# Matrix_Game_Board.net
KiCad netlist of a schematic drawn in EAGLE
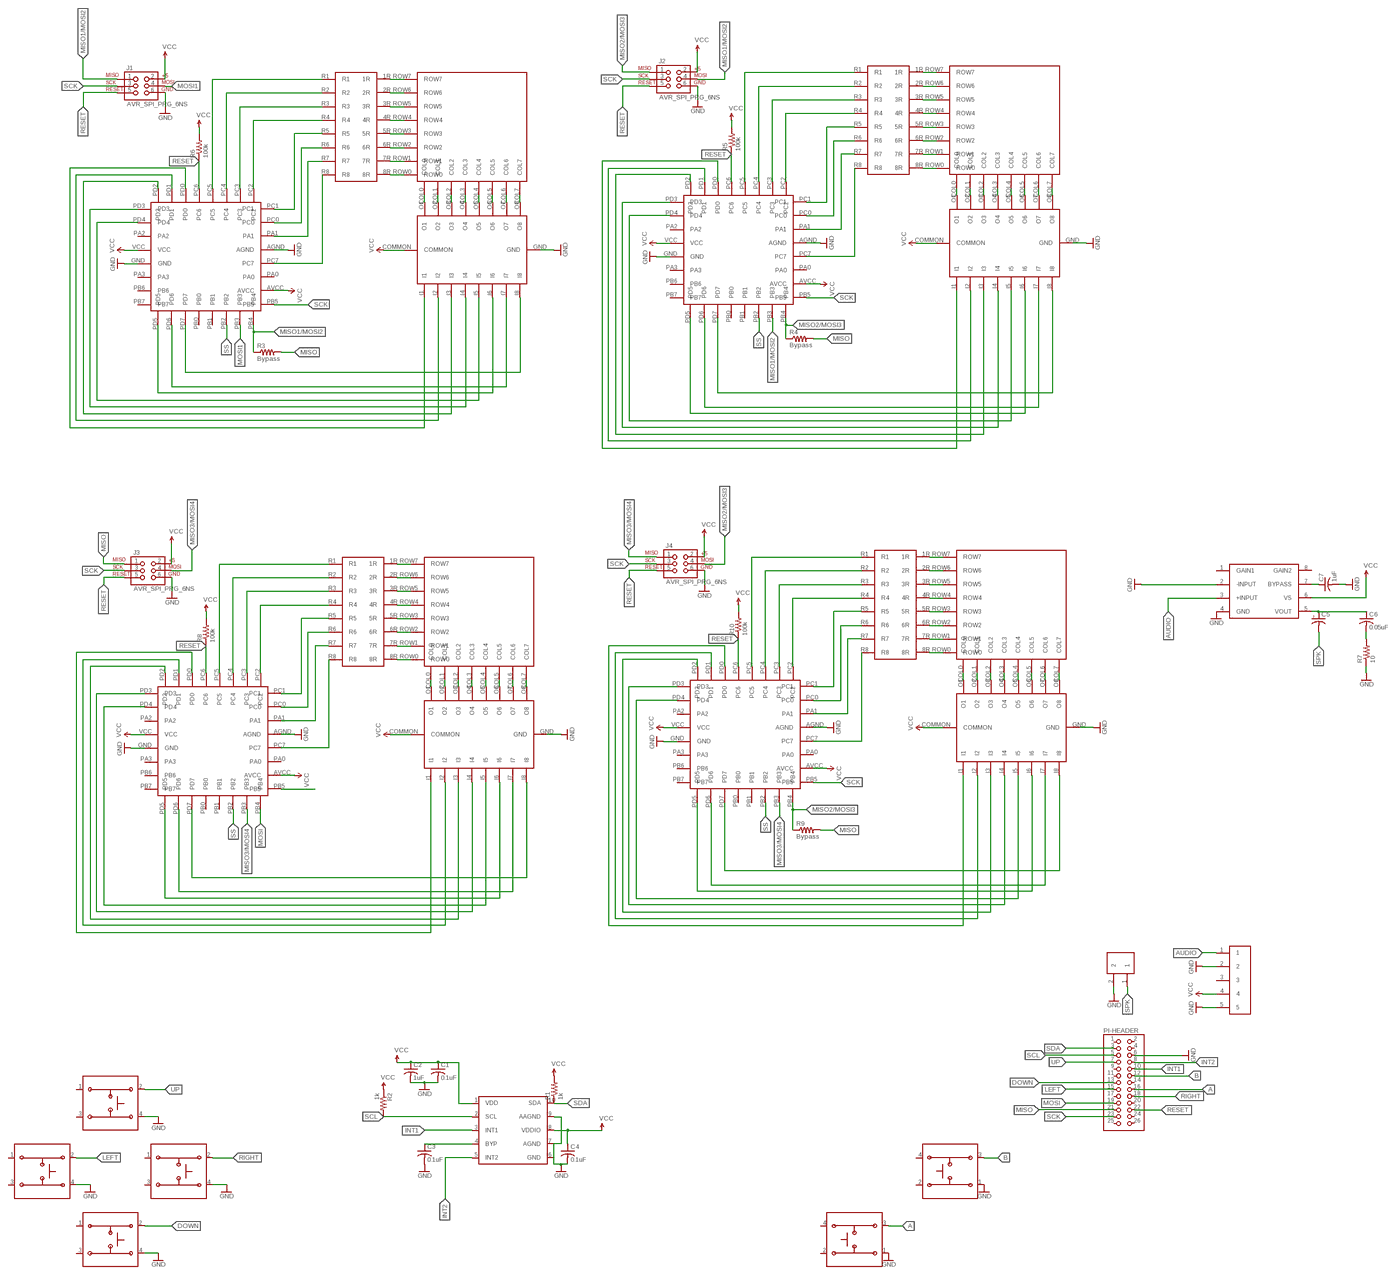
[diagram p0: schematic, sheet 1, overview]
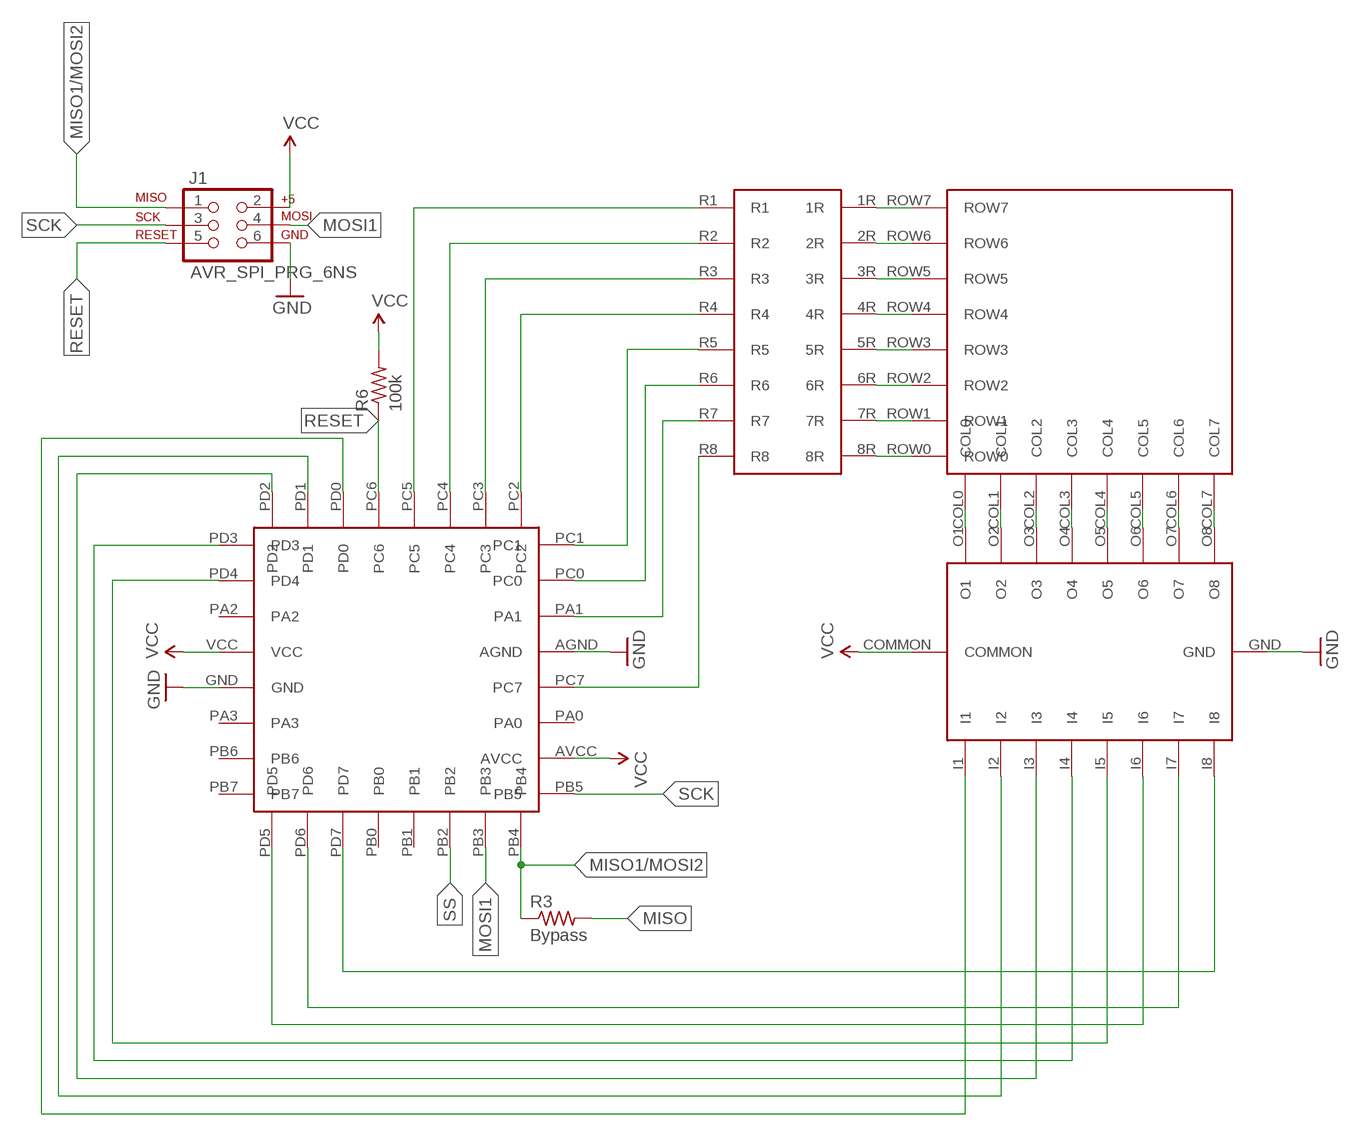
[diagram p1: schematic, sheet 1, part 1 of 4]
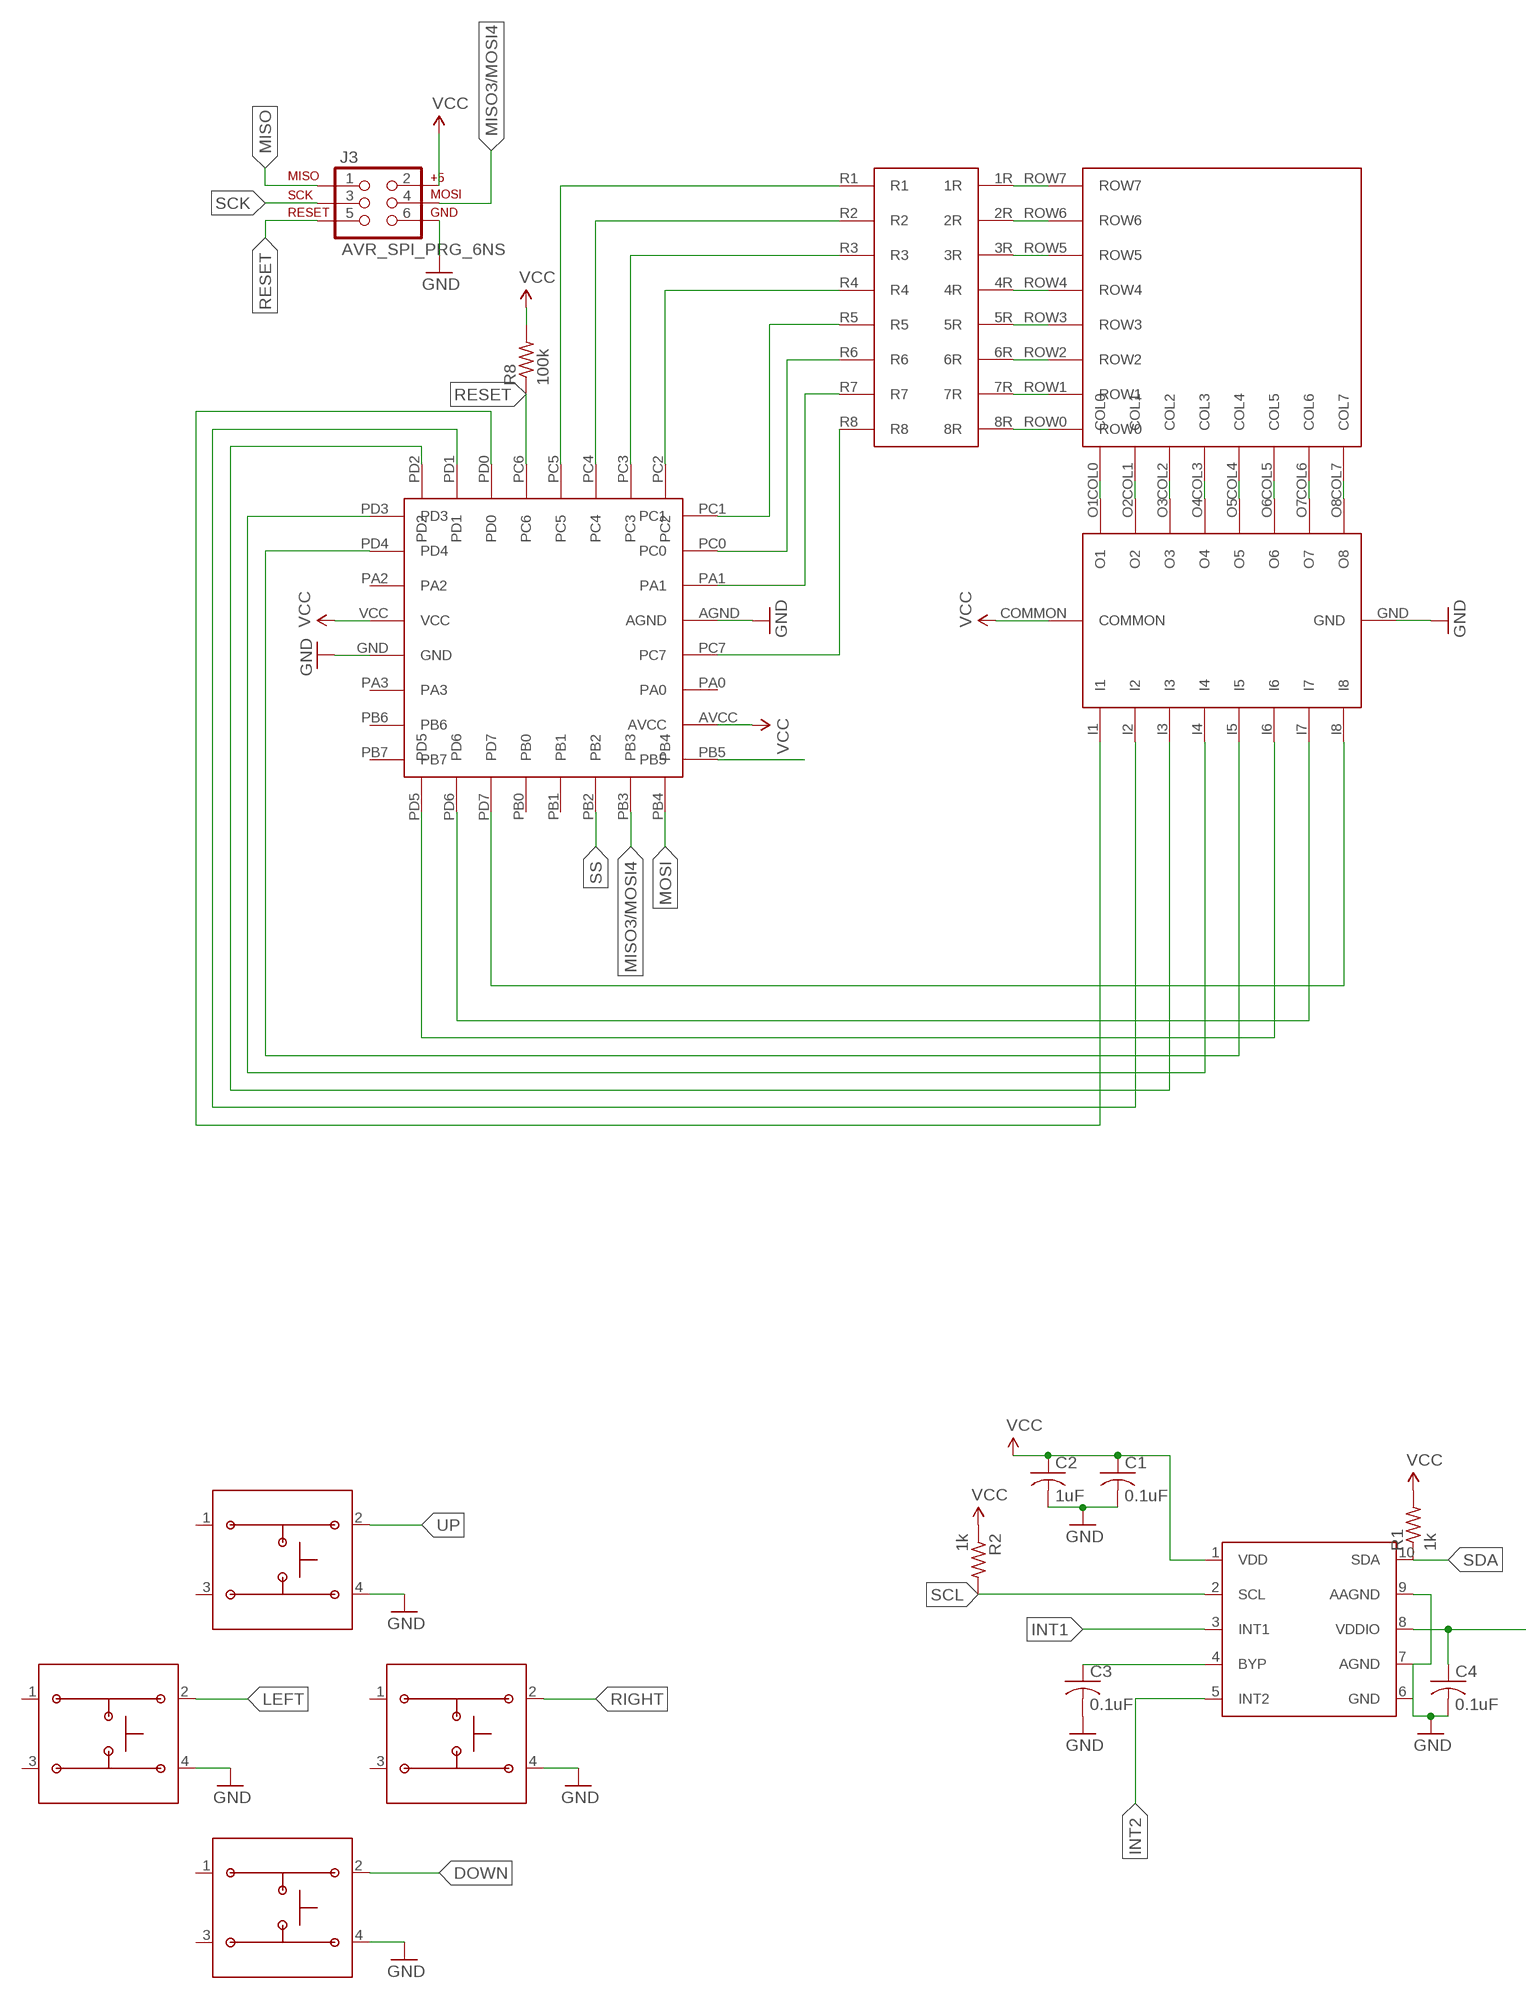
[diagram p2: schematic, sheet 1, part 2 of 4]
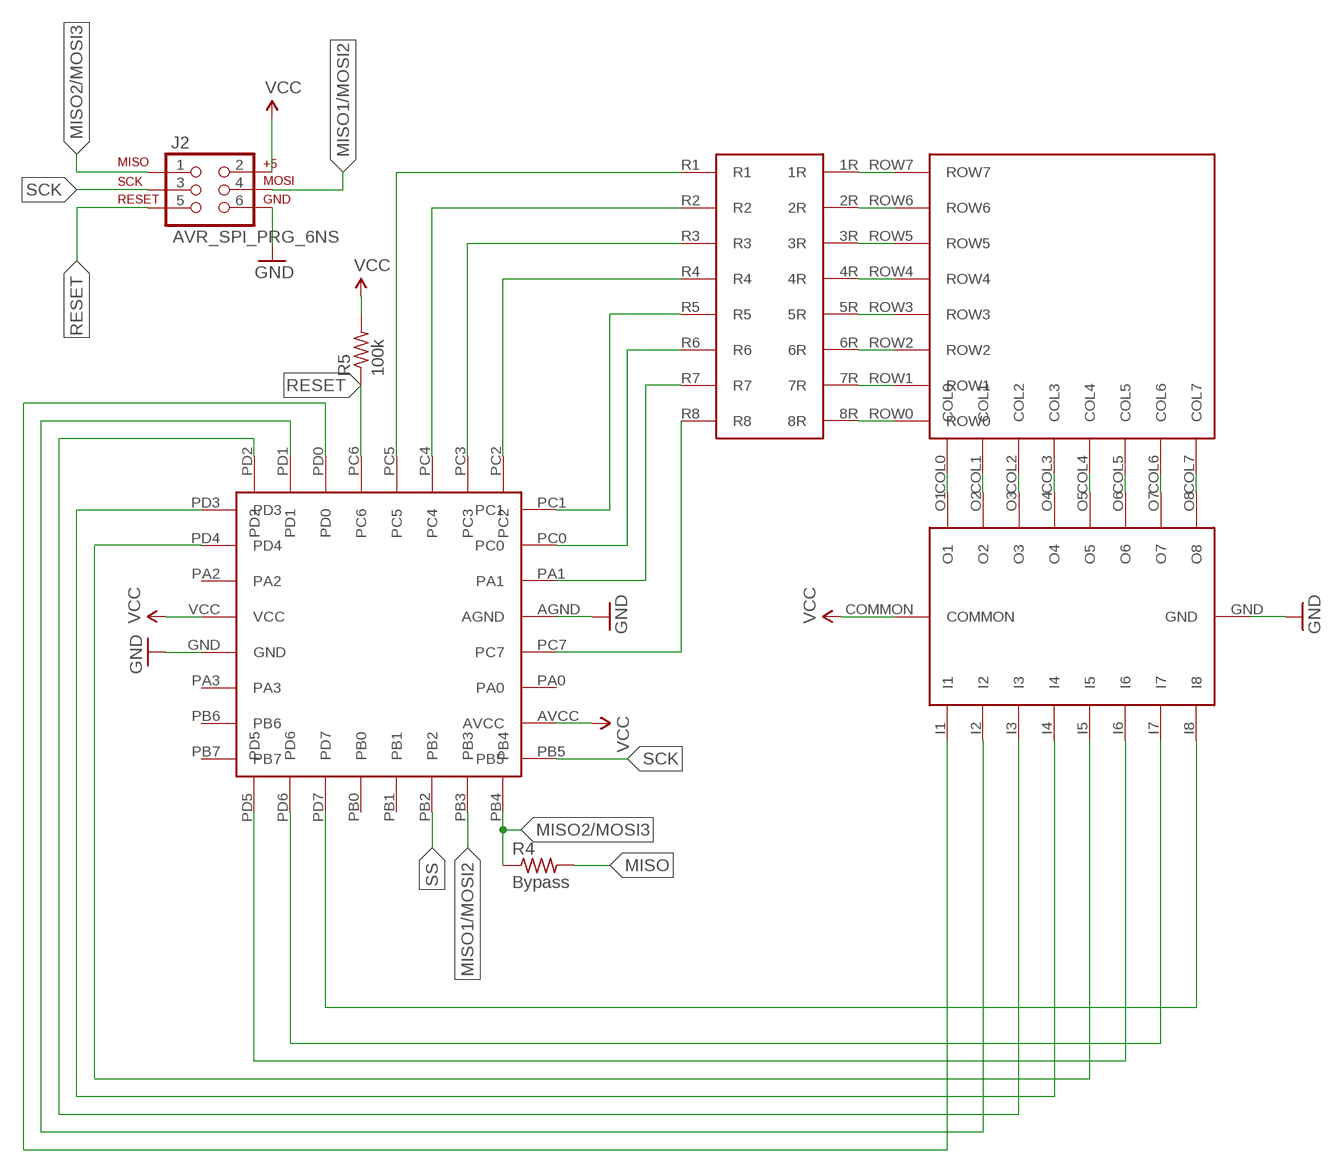
[diagram p3: schematic, sheet 1, part 3 of 4]
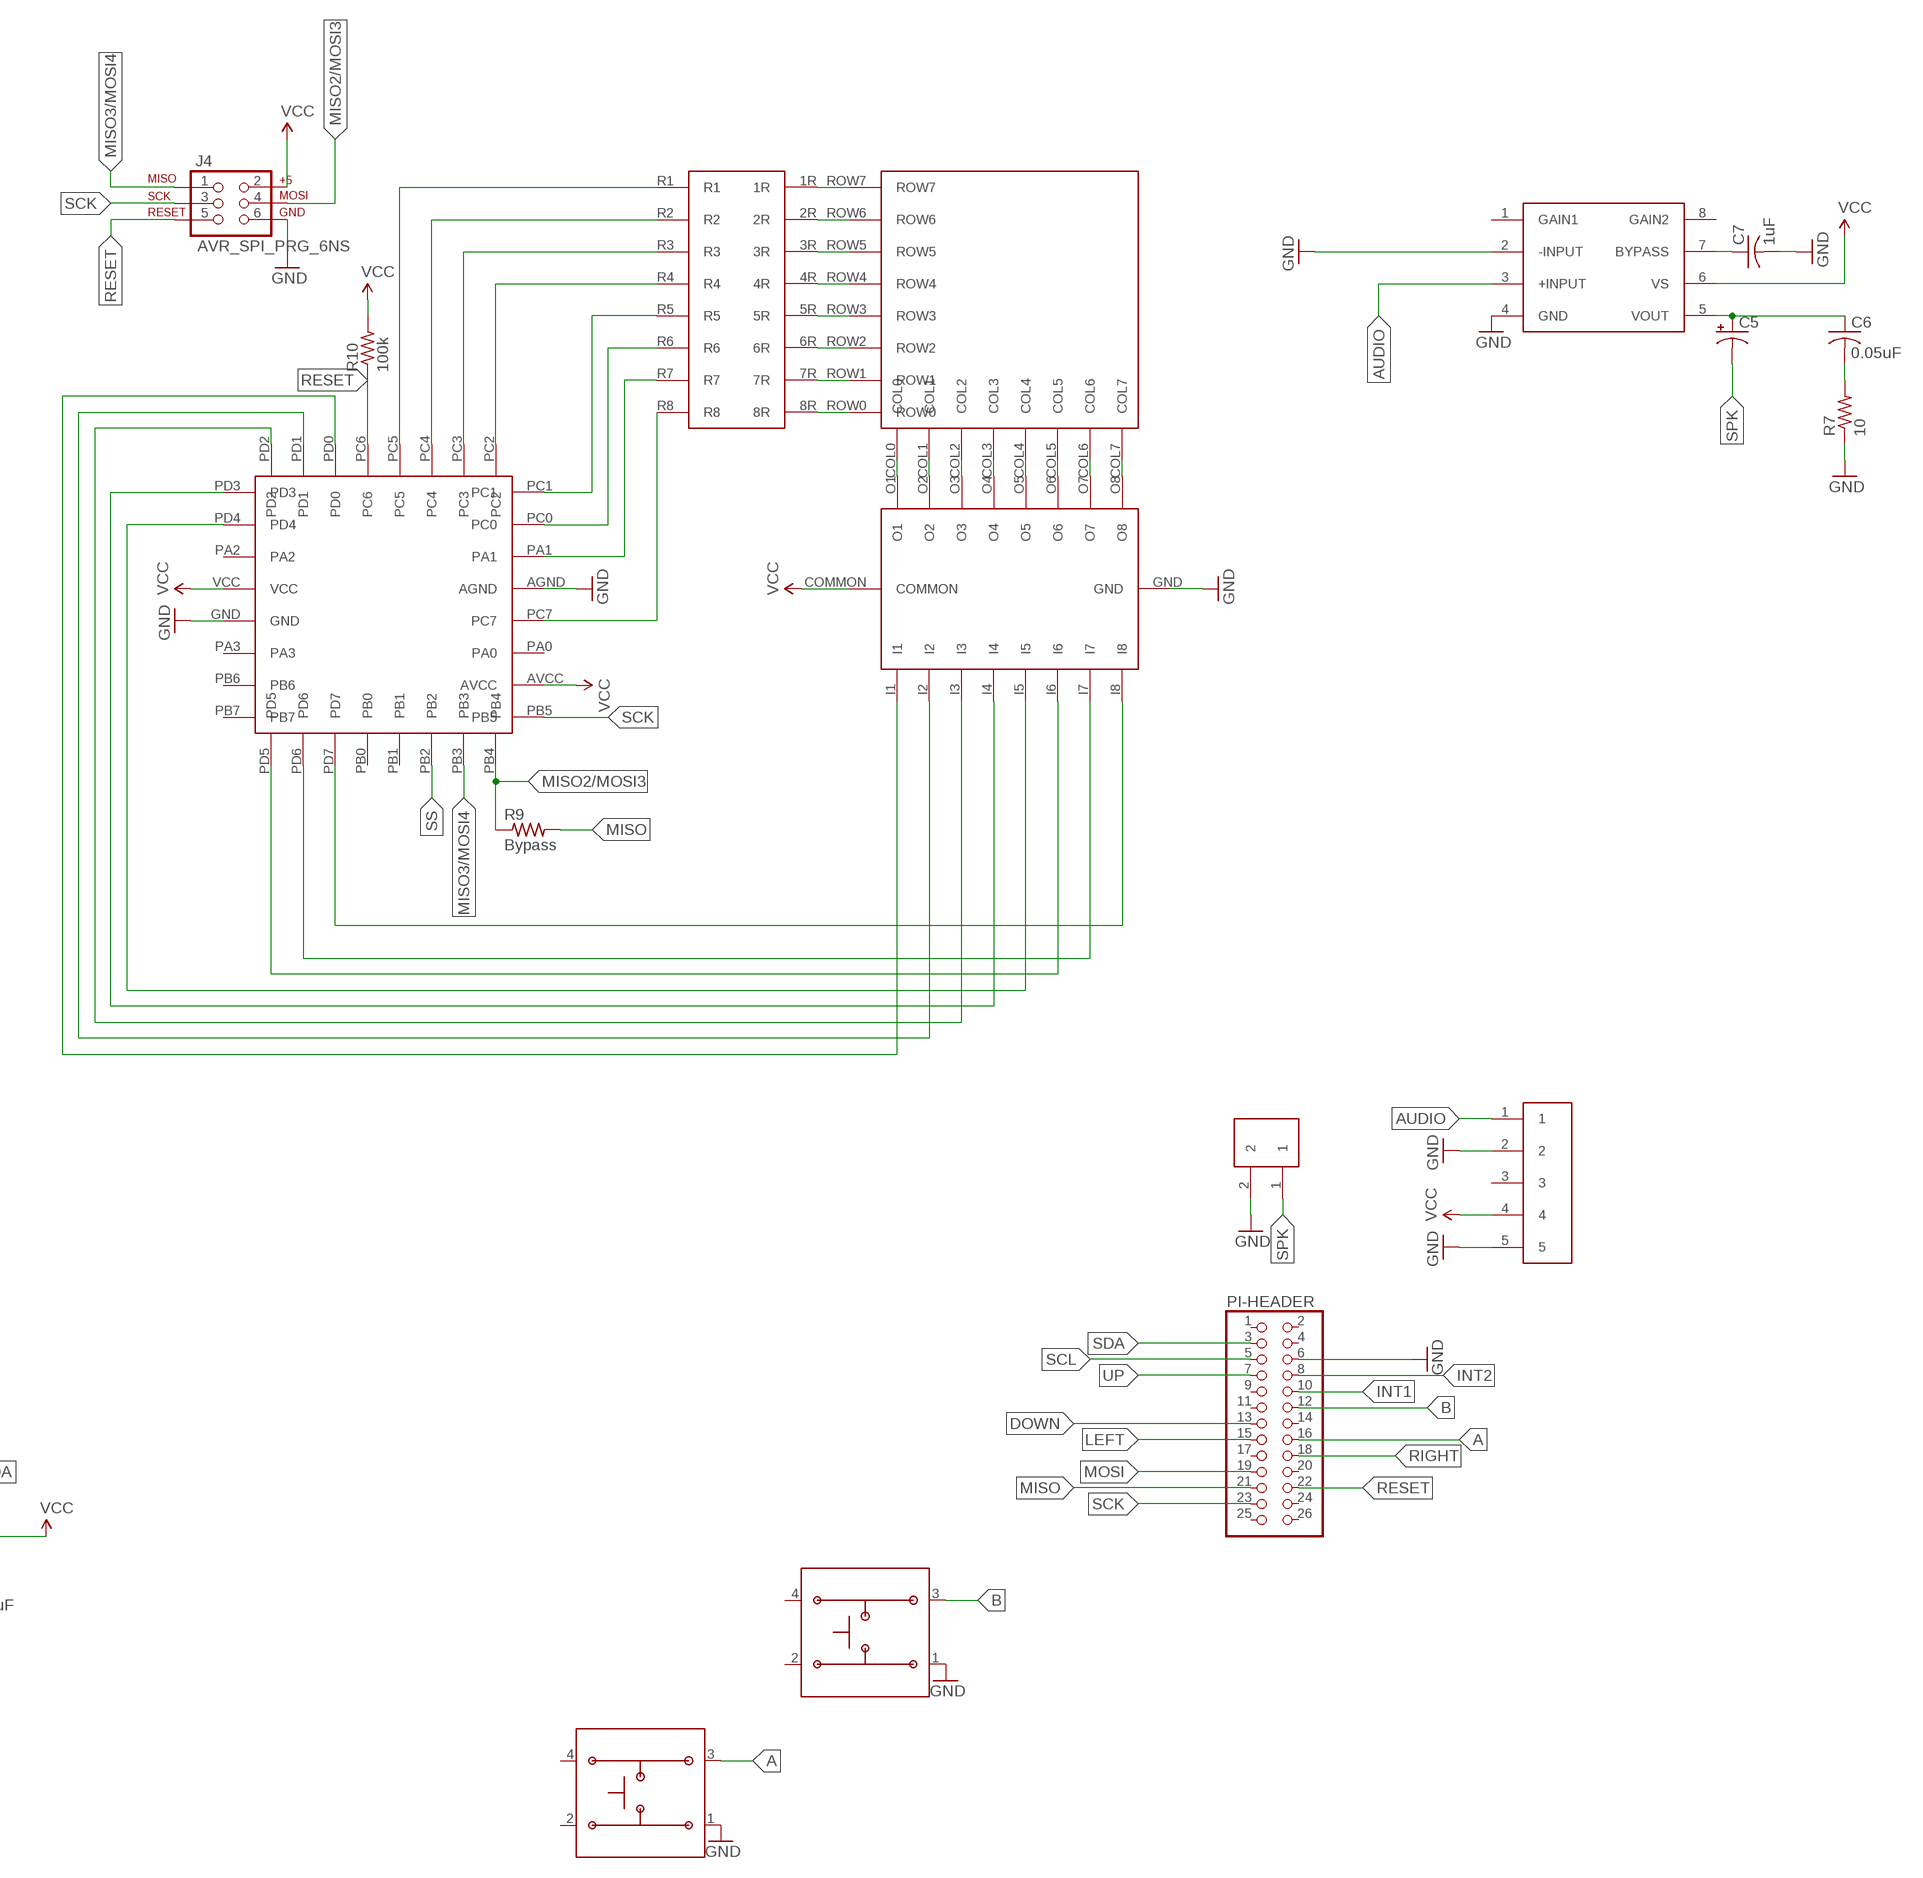
[diagram p4: schematic, sheet 1, part 4 of 4]

(export (version "E")
  (design (tool "Eeschema 10.0.6"))
  (components
    (comp (ref "C1")
      (value "0.1uF")
      (footprint "eagle-import:C0603")
      (libsource (lib "eagle-import") (part "C-USC0603"))
    )
    (comp (ref "C2")
      (value "1uF")
      (footprint "eagle-import:C0603")
      (libsource (lib "eagle-import") (part "C-USC0603"))
    )
    (comp (ref "C3")
      (value "0.1uF")
      (footprint "eagle-import:C0603")
      (libsource (lib "eagle-import") (part "C-USC0603"))
    )
    (comp (ref "C4")
      (value "0.1uF")
      (footprint "eagle-import:C0603")
      (libsource (lib "eagle-import") (part "C-USC0603"))
    )
    (comp (ref "C5")
      (value "CPOL-US153CLV-0605")
      (footprint "eagle-import:153CLV-0605")
      (libsource (lib "eagle-import") (part "CPOL-US153CLV-0605"))
    )
    (comp (ref "C6")
      (value "0.05uF")
      (footprint "eagle-import:C0603")
      (libsource (lib "eagle-import") (part "C-USC0603"))
    )
    (comp (ref "C7")
      (value "1uF")
      (footprint "eagle-import:C0603")
      (libsource (lib "eagle-import") (part "C-USC0603"))
    )
    (comp (ref "J1")
      (value "AVR_SPI_PRG_6NS")
      (footprint "eagle-import:2X3-NS")
      (libsource (lib "eagle-import") (part "AVR_SPI_PRG_6NS"))
    )
    (comp (ref "J2")
      (value "AVR_SPI_PRG_6NS")
      (footprint "eagle-import:2X3-NS")
      (libsource (lib "eagle-import") (part "AVR_SPI_PRG_6NS"))
    )
    (comp (ref "J3")
      (value "AVR_SPI_PRG_6NS")
      (footprint "eagle-import:2X3-NS")
      (libsource (lib "eagle-import") (part "AVR_SPI_PRG_6NS"))
    )
    (comp (ref "J4")
      (value "AVR_SPI_PRG_6NS")
      (footprint "eagle-import:2X3-NS")
      (libsource (lib "eagle-import") (part "AVR_SPI_PRG_6NS"))
    )
    (comp (ref "PI-HEADER")
      (value "PINHD-2X13")
      (footprint "eagle-import:2X13")
      (libsource (lib "eagle-import") (part "PINHD-2X13"))
    )
    (comp (ref "R1")
      (value "1k")
      (footprint "eagle-import:R0603")
      (libsource (lib "eagle-import") (part "R-US_R0603"))
    )
    (comp (ref "R2")
      (value "1k")
      (footprint "eagle-import:R0603")
      (libsource (lib "eagle-import") (part "R-US_R0603"))
    )
    (comp (ref "R3")
      (value "Bypass")
      (footprint "eagle-import:R0805")
      (libsource (lib "eagle-import") (part "R-US_R0805"))
    )
    (comp (ref "R4")
      (value "Bypass")
      (footprint "eagle-import:R0805")
      (libsource (lib "eagle-import") (part "R-US_R0805"))
    )
    (comp (ref "R5")
      (value "100k")
      (footprint "eagle-import:R0805")
      (libsource (lib "eagle-import") (part "R-US_R0805"))
    )
    (comp (ref "R6")
      (value "100k")
      (footprint "eagle-import:R0805")
      (libsource (lib "eagle-import") (part "R-US_R0805"))
    )
    (comp (ref "R7")
      (value "10")
      (footprint "eagle-import:R0603")
      (libsource (lib "eagle-import") (part "R-US_R0603"))
    )
    (comp (ref "R8")
      (value "100k")
      (footprint "eagle-import:R0805")
      (libsource (lib "eagle-import") (part "R-US_R0805"))
    )
    (comp (ref "R9")
      (value "Bypass")
      (footprint "eagle-import:R0805")
      (libsource (lib "eagle-import") (part "R-US_R0805"))
    )
    (comp (ref "R10")
      (value "100k")
      (footprint "eagle-import:R0805")
      (libsource (lib "eagle-import") (part "R-US_R0805"))
    )
    (comp (ref "U$1")
      (value "8X8_LED_MATRIX")
      (footprint "eagle-import:8X8_LED_MATRIX")
      (libsource (lib "eagle-import") (part "8X8_LED_MATRIX"))
    )
    (comp (ref "U$2")
      (value "RES_ARRAY")
      (footprint "eagle-import:RES_ARRAY")
      (libsource (lib "eagle-import") (part "RES_ARRAY"))
    )
    (comp (ref "U$3")
      (value "8X8_LED_MATRIX")
      (footprint "eagle-import:8X8_LED_MATRIX")
      (libsource (lib "eagle-import") (part "8X8_LED_MATRIX"))
    )
    (comp (ref "U$4")
      (value "ULN2803AFWG")
      (footprint "eagle-import:ULN2803AFWG")
      (libsource (lib "eagle-import") (part "ULN2803AFWG"))
    )
    (comp (ref "U$5")
      (value "ULN2803AFWG")
      (footprint "eagle-import:ULN2803AFWG")
      (libsource (lib "eagle-import") (part "ULN2803AFWG"))
    )
    (comp (ref "U$6")
      (value "ATTINY48")
      (footprint "eagle-import:ATTINY48")
      (libsource (lib "eagle-import") (part "ATTINY48"))
    )
    (comp (ref "U$7")
      (value "RES_ARRAY")
      (footprint "eagle-import:RES_ARRAY")
      (libsource (lib "eagle-import") (part "RES_ARRAY"))
    )
    (comp (ref "U$8")
      (value "8X8_LED_MATRIX")
      (footprint "eagle-import:8X8_LED_MATRIX")
      (libsource (lib "eagle-import") (part "8X8_LED_MATRIX"))
    )
    (comp (ref "U$9")
      (value "ATTINY48")
      (footprint "eagle-import:ATTINY48")
      (libsource (lib "eagle-import") (part "ATTINY48"))
    )
    (comp (ref "U$10")
      (value "ULN2803AFWG")
      (footprint "eagle-import:ULN2803AFWG")
      (libsource (lib "eagle-import") (part "ULN2803AFWG"))
    )
    (comp (ref "U$11")
      (value "ATTINY48")
      (footprint "eagle-import:ATTINY48")
      (libsource (lib "eagle-import") (part "ATTINY48"))
    )
    (comp (ref "U$12")
      (value "RES_ARRAY")
      (footprint "eagle-import:RES_ARRAY")
      (libsource (lib "eagle-import") (part "RES_ARRAY"))
    )
    (comp (ref "U$13")
      (value "8X8_LED_MATRIX")
      (footprint "eagle-import:8X8_LED_MATRIX")
      (libsource (lib "eagle-import") (part "8X8_LED_MATRIX"))
    )
    (comp (ref "U$14")
      (value "ULN2803AFWG")
      (footprint "eagle-import:ULN2803AFWG")
      (libsource (lib "eagle-import") (part "ULN2803AFWG"))
    )
    (comp (ref "U$15")
      (value "ATTINY48")
      (footprint "eagle-import:ATTINY48")
      (libsource (lib "eagle-import") (part "ATTINY48"))
    )
    (comp (ref "U$16")
      (value "RES_ARRAY")
      (footprint "eagle-import:RES_ARRAY")
      (libsource (lib "eagle-import") (part "RES_ARRAY"))
    )
    (comp (ref "U$17")
      (value "12X12MM_BUTTON")
      (footprint "eagle-import:12X12MM_BUTTON")
      (libsource (lib "eagle-import") (part "12X12MM_BUTTON"))
    )
    (comp (ref "U$18")
      (value "12X12MM_BUTTON")
      (footprint "eagle-import:12X12MM_BUTTON")
      (libsource (lib "eagle-import") (part "12X12MM_BUTTON"))
    )
    (comp (ref "U$19")
      (value "12X12MM_BUTTON")
      (footprint "eagle-import:12X12MM_BUTTON")
      (libsource (lib "eagle-import") (part "12X12MM_BUTTON"))
    )
    (comp (ref "U$20")
      (value "12X12MM_BUTTON")
      (footprint "eagle-import:12X12MM_BUTTON")
      (libsource (lib "eagle-import") (part "12X12MM_BUTTON"))
    )
    (comp (ref "U$21")
      (value "12X12MM_BUTTON")
      (footprint "eagle-import:12X12MM_BUTTON")
      (libsource (lib "eagle-import") (part "12X12MM_BUTTON"))
    )
    (comp (ref "U$22")
      (value "12X12MM_BUTTON")
      (footprint "eagle-import:12X12MM_BUTTON")
      (libsource (lib "eagle-import") (part "12X12MM_BUTTON"))
    )
    (comp (ref "U$23")
      (value "MMA8653FCR1")
      (footprint "eagle-import:MMA8653FCR1")
      (libsource (lib "eagle-import") (part "MMA8653FCR1"))
    )
    (comp (ref "U$25")
      (value "LM386")
      (footprint "eagle-import:LM386")
      (libsource (lib "eagle-import") (part "LM386"))
    )
    (comp (ref "U$29")
      (value "DF3_1X2")
      (footprint "eagle-import:DF3_1X2")
      (libsource (lib "eagle-import") (part "DF3_1X2"))
    )
    (comp (ref "U$30")
      (value "DF3_1X5")
      (footprint "eagle-import:DF3_1X5")
      (libsource (lib "eagle-import") (part "DF3_1X5"))
    )
  )
  (nets
    (net (code "1") (name "A") (class "Default")
      (node (ref "PI-HEADER") (pin "16") (pinfunction "16_16") (pintype "passive"))
      (node (ref "U$22") (pin "3") (pinfunction "3_3") (pintype "bidirectional"))
    )
    (net (code "2") (name "AUDIO") (class "Default")
      (node (ref "U$25") (pin "3") (pinfunction "+INPUT_3") (pintype "bidirectional"))
      (node (ref "U$30") (pin "1") (pinfunction "1_1") (pintype "bidirectional"))
    )
    (net (code "3") (name "B") (class "Default")
      (node (ref "PI-HEADER") (pin "12") (pinfunction "12_12") (pintype "passive"))
      (node (ref "U$21") (pin "3") (pinfunction "3_3") (pintype "bidirectional"))
    )
    (net (code "4") (name "DOWN") (class "Default")
      (node (ref "PI-HEADER") (pin "13") (pinfunction "13_13") (pintype "passive"))
      (node (ref "U$20") (pin "2") (pinfunction "2_2") (pintype "bidirectional"))
    )
    (net (code "5") (name "GND") (class "Default")
      (node (ref "C1") (pin "2") (pinfunction "2_2") (pintype "passive"))
      (node (ref "C2") (pin "2") (pinfunction "2_2") (pintype "passive"))
      (node (ref "C3") (pin "2") (pinfunction "2_2") (pintype "passive"))
      (node (ref "C4") (pin "2") (pinfunction "2_2") (pintype "passive"))
      (node (ref "C7") (pin "2") (pinfunction "2_2") (pintype "passive"))
      (node (ref "J1") (pin "6") (pinfunction "6_6") (pintype "passive"))
      (node (ref "J2") (pin "6") (pinfunction "6_6") (pintype "passive"))
      (node (ref "J3") (pin "6") (pinfunction "6_6") (pintype "passive"))
      (node (ref "J4") (pin "6") (pinfunction "6_6") (pintype "passive"))
      (node (ref "PI-HEADER") (pin "6") (pinfunction "6_6") (pintype "passive"))
      (node (ref "R7") (pin "1") (pinfunction "1_1") (pintype "passive"))
      (node (ref "U$10") (pin "GND") (pinfunction "GND_GND") (pintype "bidirectional"))
      (node (ref "U$11") (pin "AGND") (pinfunction "AGND_AGND") (pintype "bidirectional"))
      (node (ref "U$11") (pin "GND") (pinfunction "GND_GND") (pintype "bidirectional"))
      (node (ref "U$14") (pin "GND") (pinfunction "GND_GND") (pintype "bidirectional"))
      (node (ref "U$15") (pin "AGND") (pinfunction "AGND_AGND") (pintype "bidirectional"))
      (node (ref "U$15") (pin "GND") (pinfunction "GND_GND") (pintype "bidirectional"))
      (node (ref "U$17") (pin "4") (pinfunction "4_4") (pintype "bidirectional"))
      (node (ref "U$18") (pin "4") (pinfunction "4_4") (pintype "bidirectional"))
      (node (ref "U$19") (pin "4") (pinfunction "4_4") (pintype "bidirectional"))
      (node (ref "U$20") (pin "4") (pinfunction "4_4") (pintype "bidirectional"))
      (node (ref "U$21") (pin "1") (pinfunction "1_1") (pintype "bidirectional"))
      (node (ref "U$22") (pin "1") (pinfunction "1_1") (pintype "bidirectional"))
      (node (ref "U$23") (pin "6") (pinfunction "GND_6") (pintype "bidirectional"))
      (node (ref "U$23") (pin "7") (pinfunction "AGND_7") (pintype "bidirectional"))
      (node (ref "U$23") (pin "9") (pinfunction "AAGND_9") (pintype "bidirectional"))
      (node (ref "U$25") (pin "2") (pinfunction "-INPUT_2") (pintype "bidirectional"))
      (node (ref "U$25") (pin "4") (pinfunction "GND_4") (pintype "bidirectional"))
      (node (ref "U$29") (pin "2") (pinfunction "2_2") (pintype "bidirectional"))
      (node (ref "U$30") (pin "2") (pinfunction "2_2") (pintype "bidirectional"))
      (node (ref "U$30") (pin "5") (pinfunction "5_5") (pintype "bidirectional"))
      (node (ref "U$4") (pin "GND") (pinfunction "GND_GND") (pintype "bidirectional"))
      (node (ref "U$5") (pin "GND") (pinfunction "GND_GND") (pintype "bidirectional"))
      (node (ref "U$6") (pin "AGND") (pinfunction "AGND_AGND") (pintype "bidirectional"))
      (node (ref "U$6") (pin "GND") (pinfunction "GND_GND") (pintype "bidirectional"))
      (node (ref "U$9") (pin "AGND") (pinfunction "AGND_AGND") (pintype "bidirectional"))
      (node (ref "U$9") (pin "GND") (pinfunction "GND_GND") (pintype "bidirectional"))
    )
    (net (code "6") (name "INT1") (class "Default")
      (node (ref "PI-HEADER") (pin "10") (pinfunction "10_10") (pintype "passive"))
      (node (ref "U$23") (pin "3") (pinfunction "INT1_3") (pintype "bidirectional"))
    )
    (net (code "7") (name "INT2") (class "Default")
      (node (ref "PI-HEADER") (pin "8") (pinfunction "8_8") (pintype "passive"))
      (node (ref "U$23") (pin "5") (pinfunction "INT2_5") (pintype "bidirectional"))
    )
    (net (code "8") (name "LEFT") (class "Default")
      (node (ref "PI-HEADER") (pin "15") (pinfunction "15_15") (pintype "passive"))
      (node (ref "U$18") (pin "2") (pinfunction "2_2") (pintype "bidirectional"))
    )
    (net (code "9") (name "MISO") (class "Default")
      (node (ref "J3") (pin "1") (pinfunction "1_1") (pintype "passive"))
      (node (ref "PI-HEADER") (pin "21") (pinfunction "21_21") (pintype "passive"))
      (node (ref "R3") (pin "2") (pinfunction "2_2") (pintype "passive"))
      (node (ref "R4") (pin "2") (pinfunction "2_2") (pintype "passive"))
      (node (ref "R9") (pin "2") (pinfunction "2_2") (pintype "passive"))
    )
    (net (code "10") (name "MISO1{slash}MOSI2") (class "Default")
      (node (ref "J1") (pin "1") (pinfunction "1_1") (pintype "passive"))
      (node (ref "J2") (pin "4") (pinfunction "4_4") (pintype "passive"))
      (node (ref "R3") (pin "1") (pinfunction "1_1") (pintype "passive"))
      (node (ref "U$6") (pin "PB3") (pinfunction "PB3_PB3") (pintype "bidirectional"))
      (node (ref "U$9") (pin "PB4") (pinfunction "PB4_PB4") (pintype "bidirectional"))
    )
    (net (code "11") (name "MISO2{slash}MOSI3") (class "Default")
      (node (ref "J2") (pin "1") (pinfunction "1_1") (pintype "passive"))
      (node (ref "J4") (pin "4") (pinfunction "4_4") (pintype "passive"))
      (node (ref "R4") (pin "1") (pinfunction "1_1") (pintype "passive"))
      (node (ref "R9") (pin "1") (pinfunction "1_1") (pintype "passive"))
      (node (ref "U$15") (pin "PB4") (pinfunction "PB4_PB4") (pintype "bidirectional"))
      (node (ref "U$6") (pin "PB4") (pinfunction "PB4_PB4") (pintype "bidirectional"))
    )
    (net (code "12") (name "MISO3{slash}MOSI4") (class "Default")
      (node (ref "J3") (pin "4") (pinfunction "4_4") (pintype "passive"))
      (node (ref "J4") (pin "1") (pinfunction "1_1") (pintype "passive"))
      (node (ref "U$11") (pin "PB3") (pinfunction "PB3_PB3") (pintype "bidirectional"))
      (node (ref "U$15") (pin "PB3") (pinfunction "PB3_PB3") (pintype "bidirectional"))
    )
    (net (code "13") (name "MOSI") (class "Default")
      (node (ref "PI-HEADER") (pin "19") (pinfunction "19_19") (pintype "passive"))
      (node (ref "U$11") (pin "PB4") (pinfunction "PB4_PB4") (pintype "bidirectional"))
    )
    (net (code "14") (name "MOSI1") (class "Default")
      (node (ref "J1") (pin "4") (pinfunction "4_4") (pintype "passive"))
      (node (ref "U$9") (pin "PB3") (pinfunction "PB3_PB3") (pintype "bidirectional"))
    )
    (net (code "15") (name "Net-(C6-Pad2)") (class "Default")
      (node (ref "C6") (pin "2") (pinfunction "2_2") (pintype "passive"))
      (node (ref "R7") (pin "2") (pinfunction "2_2") (pintype "passive"))
    )
    (net (code "16") (name "Net-(U$1-PadCOL0)") (class "Default")
      (node (ref "U$1") (pin "COL0") (pinfunction "COL0_COL0") (pintype "bidirectional"))
      (node (ref "U$5") (pin "O1") (pinfunction "O1_O1") (pintype "bidirectional"))
    )
    (net (code "17") (name "Net-(U$1-PadCOL1)") (class "Default")
      (node (ref "U$1") (pin "COL1") (pinfunction "COL1_COL1") (pintype "bidirectional"))
      (node (ref "U$5") (pin "O2") (pinfunction "O2_O2") (pintype "bidirectional"))
    )
    (net (code "18") (name "Net-(U$1-PadCOL2)") (class "Default")
      (node (ref "U$1") (pin "COL2") (pinfunction "COL2_COL2") (pintype "bidirectional"))
      (node (ref "U$5") (pin "O3") (pinfunction "O3_O3") (pintype "bidirectional"))
    )
    (net (code "19") (name "Net-(U$1-PadCOL3)") (class "Default")
      (node (ref "U$1") (pin "COL3") (pinfunction "COL3_COL3") (pintype "bidirectional"))
      (node (ref "U$5") (pin "O4") (pinfunction "O4_O4") (pintype "bidirectional"))
    )
    (net (code "20") (name "Net-(U$1-PadCOL4)") (class "Default")
      (node (ref "U$1") (pin "COL4") (pinfunction "COL4_COL4") (pintype "bidirectional"))
      (node (ref "U$5") (pin "O5") (pinfunction "O5_O5") (pintype "bidirectional"))
    )
    (net (code "21") (name "Net-(U$1-PadCOL5)") (class "Default")
      (node (ref "U$1") (pin "COL5") (pinfunction "COL5_COL5") (pintype "bidirectional"))
      (node (ref "U$5") (pin "O6") (pinfunction "O6_O6") (pintype "bidirectional"))
    )
    (net (code "22") (name "Net-(U$1-PadCOL6)") (class "Default")
      (node (ref "U$1") (pin "COL6") (pinfunction "COL6_COL6") (pintype "bidirectional"))
      (node (ref "U$5") (pin "O7") (pinfunction "O7_O7") (pintype "bidirectional"))
    )
    (net (code "23") (name "Net-(U$1-PadCOL7)") (class "Default")
      (node (ref "U$1") (pin "COL7") (pinfunction "COL7_COL7") (pintype "bidirectional"))
      (node (ref "U$5") (pin "O8") (pinfunction "O8_O8") (pintype "bidirectional"))
    )
    (net (code "24") (name "Net-(U$1-PadROW0)") (class "Default")
      (node (ref "U$1") (pin "ROW0") (pinfunction "ROW0_ROW0") (pintype "bidirectional"))
      (node (ref "U$2") (pin "8R") (pinfunction "8R_8R") (pintype "bidirectional"))
    )
    (net (code "25") (name "Net-(U$1-PadROW1)") (class "Default")
      (node (ref "U$1") (pin "ROW1") (pinfunction "ROW1_ROW1") (pintype "bidirectional"))
      (node (ref "U$2") (pin "7R") (pinfunction "7R_7R") (pintype "bidirectional"))
    )
    (net (code "26") (name "Net-(U$1-PadROW2)") (class "Default")
      (node (ref "U$1") (pin "ROW2") (pinfunction "ROW2_ROW2") (pintype "bidirectional"))
      (node (ref "U$2") (pin "6R") (pinfunction "6R_6R") (pintype "bidirectional"))
    )
    (net (code "27") (name "Net-(U$1-PadROW3)") (class "Default")
      (node (ref "U$1") (pin "ROW3") (pinfunction "ROW3_ROW3") (pintype "bidirectional"))
      (node (ref "U$2") (pin "5R") (pinfunction "5R_5R") (pintype "bidirectional"))
    )
    (net (code "28") (name "Net-(U$1-PadROW4)") (class "Default")
      (node (ref "U$1") (pin "ROW4") (pinfunction "ROW4_ROW4") (pintype "bidirectional"))
      (node (ref "U$2") (pin "4R") (pinfunction "4R_4R") (pintype "bidirectional"))
    )
    (net (code "29") (name "Net-(U$1-PadROW5)") (class "Default")
      (node (ref "U$1") (pin "ROW5") (pinfunction "ROW5_ROW5") (pintype "bidirectional"))
      (node (ref "U$2") (pin "3R") (pinfunction "3R_3R") (pintype "bidirectional"))
    )
    (net (code "30") (name "Net-(U$1-PadROW6)") (class "Default")
      (node (ref "U$1") (pin "ROW6") (pinfunction "ROW6_ROW6") (pintype "bidirectional"))
      (node (ref "U$2") (pin "2R") (pinfunction "2R_2R") (pintype "bidirectional"))
    )
    (net (code "31") (name "Net-(U$1-PadROW7)") (class "Default")
      (node (ref "U$1") (pin "ROW7") (pinfunction "ROW7_ROW7") (pintype "bidirectional"))
      (node (ref "U$2") (pin "1R") (pinfunction "1R_1R") (pintype "bidirectional"))
    )
    (net (code "32") (name "Net-(U$2-PadR1)") (class "Default")
      (node (ref "U$2") (pin "R1") (pinfunction "R1_R1") (pintype "bidirectional"))
      (node (ref "U$9") (pin "PC5") (pinfunction "PC5_PC5") (pintype "bidirectional"))
    )
    (net (code "33") (name "Net-(U$2-PadR2)") (class "Default")
      (node (ref "U$2") (pin "R2") (pinfunction "R2_R2") (pintype "bidirectional"))
      (node (ref "U$9") (pin "PC4") (pinfunction "PC4_PC4") (pintype "bidirectional"))
    )
    (net (code "34") (name "Net-(U$2-PadR3)") (class "Default")
      (node (ref "U$2") (pin "R3") (pinfunction "R3_R3") (pintype "bidirectional"))
      (node (ref "U$9") (pin "PC3") (pinfunction "PC3_PC3") (pintype "bidirectional"))
    )
    (net (code "35") (name "Net-(U$2-PadR4)") (class "Default")
      (node (ref "U$2") (pin "R4") (pinfunction "R4_R4") (pintype "bidirectional"))
      (node (ref "U$9") (pin "PC2") (pinfunction "PC2_PC2") (pintype "bidirectional"))
    )
    (net (code "36") (name "Net-(U$2-PadR5)") (class "Default")
      (node (ref "U$2") (pin "R5") (pinfunction "R5_R5") (pintype "bidirectional"))
      (node (ref "U$9") (pin "PC1") (pinfunction "PC1_PC1") (pintype "bidirectional"))
    )
    (net (code "37") (name "Net-(U$2-PadR6)") (class "Default")
      (node (ref "U$2") (pin "R6") (pinfunction "R6_R6") (pintype "bidirectional"))
      (node (ref "U$9") (pin "PC0") (pinfunction "PC0_PC0") (pintype "bidirectional"))
    )
    (net (code "38") (name "Net-(U$2-PadR7)") (class "Default")
      (node (ref "U$2") (pin "R7") (pinfunction "R7_R7") (pintype "bidirectional"))
      (node (ref "U$9") (pin "PA1") (pinfunction "PA1_PA1") (pintype "bidirectional"))
    )
    (net (code "39") (name "Net-(U$2-PadR8)") (class "Default")
      (node (ref "U$2") (pin "R8") (pinfunction "R8_R8") (pintype "bidirectional"))
      (node (ref "U$9") (pin "PC7") (pinfunction "PC7_PC7") (pintype "bidirectional"))
    )
    (net (code "40") (name "Net-(U$3-PadCOL0)") (class "Default")
      (node (ref "U$3") (pin "COL0") (pinfunction "COL0_COL0") (pintype "bidirectional"))
      (node (ref "U$4") (pin "O1") (pinfunction "O1_O1") (pintype "bidirectional"))
    )
    (net (code "41") (name "Net-(U$3-PadCOL1)") (class "Default")
      (node (ref "U$3") (pin "COL1") (pinfunction "COL1_COL1") (pintype "bidirectional"))
      (node (ref "U$4") (pin "O2") (pinfunction "O2_O2") (pintype "bidirectional"))
    )
    (net (code "42") (name "Net-(U$3-PadCOL2)") (class "Default")
      (node (ref "U$3") (pin "COL2") (pinfunction "COL2_COL2") (pintype "bidirectional"))
      (node (ref "U$4") (pin "O3") (pinfunction "O3_O3") (pintype "bidirectional"))
    )
    (net (code "43") (name "Net-(U$3-PadCOL3)") (class "Default")
      (node (ref "U$3") (pin "COL3") (pinfunction "COL3_COL3") (pintype "bidirectional"))
      (node (ref "U$4") (pin "O4") (pinfunction "O4_O4") (pintype "bidirectional"))
    )
    (net (code "44") (name "Net-(U$3-PadCOL4)") (class "Default")
      (node (ref "U$3") (pin "COL4") (pinfunction "COL4_COL4") (pintype "bidirectional"))
      (node (ref "U$4") (pin "O5") (pinfunction "O5_O5") (pintype "bidirectional"))
    )
    (net (code "45") (name "Net-(U$3-PadCOL5)") (class "Default")
      (node (ref "U$3") (pin "COL5") (pinfunction "COL5_COL5") (pintype "bidirectional"))
      (node (ref "U$4") (pin "O6") (pinfunction "O6_O6") (pintype "bidirectional"))
    )
    (net (code "46") (name "Net-(U$3-PadCOL6)") (class "Default")
      (node (ref "U$3") (pin "COL6") (pinfunction "COL6_COL6") (pintype "bidirectional"))
      (node (ref "U$4") (pin "O7") (pinfunction "O7_O7") (pintype "bidirectional"))
    )
    (net (code "47") (name "Net-(U$3-PadCOL7)") (class "Default")
      (node (ref "U$3") (pin "COL7") (pinfunction "COL7_COL7") (pintype "bidirectional"))
      (node (ref "U$4") (pin "O8") (pinfunction "O8_O8") (pintype "bidirectional"))
    )
    (net (code "48") (name "Net-(U$3-PadROW0)") (class "Default")
      (node (ref "U$3") (pin "ROW0") (pinfunction "ROW0_ROW0") (pintype "bidirectional"))
      (node (ref "U$7") (pin "8R") (pinfunction "8R_8R") (pintype "bidirectional"))
    )
    (net (code "49") (name "Net-(U$3-PadROW1)") (class "Default")
      (node (ref "U$3") (pin "ROW1") (pinfunction "ROW1_ROW1") (pintype "bidirectional"))
      (node (ref "U$7") (pin "7R") (pinfunction "7R_7R") (pintype "bidirectional"))
    )
    (net (code "50") (name "Net-(U$3-PadROW2)") (class "Default")
      (node (ref "U$3") (pin "ROW2") (pinfunction "ROW2_ROW2") (pintype "bidirectional"))
      (node (ref "U$7") (pin "6R") (pinfunction "6R_6R") (pintype "bidirectional"))
    )
    (net (code "51") (name "Net-(U$3-PadROW3)") (class "Default")
      (node (ref "U$3") (pin "ROW3") (pinfunction "ROW3_ROW3") (pintype "bidirectional"))
      (node (ref "U$7") (pin "5R") (pinfunction "5R_5R") (pintype "bidirectional"))
    )
    (net (code "52") (name "Net-(U$3-PadROW4)") (class "Default")
      (node (ref "U$3") (pin "ROW4") (pinfunction "ROW4_ROW4") (pintype "bidirectional"))
      (node (ref "U$7") (pin "4R") (pinfunction "4R_4R") (pintype "bidirectional"))
    )
    (net (code "53") (name "Net-(U$3-PadROW5)") (class "Default")
      (node (ref "U$3") (pin "ROW5") (pinfunction "ROW5_ROW5") (pintype "bidirectional"))
      (node (ref "U$7") (pin "3R") (pinfunction "3R_3R") (pintype "bidirectional"))
    )
    (net (code "54") (name "Net-(U$3-PadROW6)") (class "Default")
      (node (ref "U$3") (pin "ROW6") (pinfunction "ROW6_ROW6") (pintype "bidirectional"))
      (node (ref "U$7") (pin "2R") (pinfunction "2R_2R") (pintype "bidirectional"))
    )
    (net (code "55") (name "Net-(U$3-PadROW7)") (class "Default")
      (node (ref "U$3") (pin "ROW7") (pinfunction "ROW7_ROW7") (pintype "bidirectional"))
      (node (ref "U$7") (pin "1R") (pinfunction "1R_1R") (pintype "bidirectional"))
    )
    (net (code "56") (name "Net-(U$4-PadI1)") (class "Default")
      (node (ref "U$4") (pin "I1") (pinfunction "I1_I1") (pintype "bidirectional"))
      (node (ref "U$6") (pin "PD0") (pinfunction "PD0_PD0") (pintype "bidirectional"))
    )
    (net (code "57") (name "Net-(U$4-PadI2)") (class "Default")
      (node (ref "U$4") (pin "I2") (pinfunction "I2_I2") (pintype "bidirectional"))
      (node (ref "U$6") (pin "PD1") (pinfunction "PD1_PD1") (pintype "bidirectional"))
    )
    (net (code "58") (name "Net-(U$4-PadI3)") (class "Default")
      (node (ref "U$4") (pin "I3") (pinfunction "I3_I3") (pintype "bidirectional"))
      (node (ref "U$6") (pin "PD2") (pinfunction "PD2_PD2") (pintype "bidirectional"))
    )
    (net (code "59") (name "Net-(U$4-PadI4)") (class "Default")
      (node (ref "U$4") (pin "I4") (pinfunction "I4_I4") (pintype "bidirectional"))
      (node (ref "U$6") (pin "PD3") (pinfunction "PD3_PD3") (pintype "bidirectional"))
    )
    (net (code "60") (name "Net-(U$4-PadI5)") (class "Default")
      (node (ref "U$4") (pin "I5") (pinfunction "I5_I5") (pintype "bidirectional"))
      (node (ref "U$6") (pin "PD4") (pinfunction "PD4_PD4") (pintype "bidirectional"))
    )
    (net (code "61") (name "Net-(U$4-PadI6)") (class "Default")
      (node (ref "U$4") (pin "I6") (pinfunction "I6_I6") (pintype "bidirectional"))
      (node (ref "U$6") (pin "PD5") (pinfunction "PD5_PD5") (pintype "bidirectional"))
    )
    (net (code "62") (name "Net-(U$4-PadI7)") (class "Default")
      (node (ref "U$4") (pin "I7") (pinfunction "I7_I7") (pintype "bidirectional"))
      (node (ref "U$6") (pin "PD6") (pinfunction "PD6_PD6") (pintype "bidirectional"))
    )
    (net (code "63") (name "Net-(U$4-PadI8)") (class "Default")
      (node (ref "U$4") (pin "I8") (pinfunction "I8_I8") (pintype "bidirectional"))
      (node (ref "U$6") (pin "PD7") (pinfunction "PD7_PD7") (pintype "bidirectional"))
    )
    (net (code "64") (name "Net-(U$5-PadI1)") (class "Default")
      (node (ref "U$5") (pin "I1") (pinfunction "I1_I1") (pintype "bidirectional"))
      (node (ref "U$9") (pin "PD0") (pinfunction "PD0_PD0") (pintype "bidirectional"))
    )
    (net (code "65") (name "Net-(U$5-PadI2)") (class "Default")
      (node (ref "U$5") (pin "I2") (pinfunction "I2_I2") (pintype "bidirectional"))
      (node (ref "U$9") (pin "PD1") (pinfunction "PD1_PD1") (pintype "bidirectional"))
    )
    (net (code "66") (name "Net-(U$5-PadI3)") (class "Default")
      (node (ref "U$5") (pin "I3") (pinfunction "I3_I3") (pintype "bidirectional"))
      (node (ref "U$9") (pin "PD2") (pinfunction "PD2_PD2") (pintype "bidirectional"))
    )
    (net (code "67") (name "Net-(U$5-PadI4)") (class "Default")
      (node (ref "U$5") (pin "I4") (pinfunction "I4_I4") (pintype "bidirectional"))
      (node (ref "U$9") (pin "PD3") (pinfunction "PD3_PD3") (pintype "bidirectional"))
    )
    (net (code "68") (name "Net-(U$5-PadI5)") (class "Default")
      (node (ref "U$5") (pin "I5") (pinfunction "I5_I5") (pintype "bidirectional"))
      (node (ref "U$9") (pin "PD4") (pinfunction "PD4_PD4") (pintype "bidirectional"))
    )
    (net (code "69") (name "Net-(U$5-PadI6)") (class "Default")
      (node (ref "U$5") (pin "I6") (pinfunction "I6_I6") (pintype "bidirectional"))
      (node (ref "U$9") (pin "PD5") (pinfunction "PD5_PD5") (pintype "bidirectional"))
    )
    (net (code "70") (name "Net-(U$5-PadI7)") (class "Default")
      (node (ref "U$5") (pin "I7") (pinfunction "I7_I7") (pintype "bidirectional"))
      (node (ref "U$9") (pin "PD6") (pinfunction "PD6_PD6") (pintype "bidirectional"))
    )
    (net (code "71") (name "Net-(U$5-PadI8)") (class "Default")
      (node (ref "U$5") (pin "I8") (pinfunction "I8_I8") (pintype "bidirectional"))
      (node (ref "U$9") (pin "PD7") (pinfunction "PD7_PD7") (pintype "bidirectional"))
    )
    (net (code "72") (name "Net-(U$6-PadPA1)") (class "Default")
      (node (ref "U$6") (pin "PA1") (pinfunction "PA1_PA1") (pintype "bidirectional"))
      (node (ref "U$7") (pin "R7") (pinfunction "R7_R7") (pintype "bidirectional"))
    )
    (net (code "73") (name "Net-(U$6-PadPC0)") (class "Default")
      (node (ref "U$6") (pin "PC0") (pinfunction "PC0_PC0") (pintype "bidirectional"))
      (node (ref "U$7") (pin "R6") (pinfunction "R6_R6") (pintype "bidirectional"))
    )
    (net (code "74") (name "Net-(U$6-PadPC1)") (class "Default")
      (node (ref "U$6") (pin "PC1") (pinfunction "PC1_PC1") (pintype "bidirectional"))
      (node (ref "U$7") (pin "R5") (pinfunction "R5_R5") (pintype "bidirectional"))
    )
    (net (code "75") (name "Net-(U$6-PadPC2)") (class "Default")
      (node (ref "U$6") (pin "PC2") (pinfunction "PC2_PC2") (pintype "bidirectional"))
      (node (ref "U$7") (pin "R4") (pinfunction "R4_R4") (pintype "bidirectional"))
    )
    (net (code "76") (name "Net-(U$6-PadPC3)") (class "Default")
      (node (ref "U$6") (pin "PC3") (pinfunction "PC3_PC3") (pintype "bidirectional"))
      (node (ref "U$7") (pin "R3") (pinfunction "R3_R3") (pintype "bidirectional"))
    )
    (net (code "77") (name "Net-(U$6-PadPC4)") (class "Default")
      (node (ref "U$6") (pin "PC4") (pinfunction "PC4_PC4") (pintype "bidirectional"))
      (node (ref "U$7") (pin "R2") (pinfunction "R2_R2") (pintype "bidirectional"))
    )
    (net (code "78") (name "Net-(U$6-PadPC5)") (class "Default")
      (node (ref "U$6") (pin "PC5") (pinfunction "PC5_PC5") (pintype "bidirectional"))
      (node (ref "U$7") (pin "R1") (pinfunction "R1_R1") (pintype "bidirectional"))
    )
    (net (code "79") (name "Net-(U$6-PadPC7)") (class "Default")
      (node (ref "U$6") (pin "PC7") (pinfunction "PC7_PC7") (pintype "bidirectional"))
      (node (ref "U$7") (pin "R8") (pinfunction "R8_R8") (pintype "bidirectional"))
    )
    (net (code "80") (name "Net-(U$10-PadI1)") (class "Default")
      (node (ref "U$10") (pin "I1") (pinfunction "I1_I1") (pintype "bidirectional"))
      (node (ref "U$11") (pin "PD0") (pinfunction "PD0_PD0") (pintype "bidirectional"))
    )
    (net (code "81") (name "Net-(U$10-PadI2)") (class "Default")
      (node (ref "U$10") (pin "I2") (pinfunction "I2_I2") (pintype "bidirectional"))
      (node (ref "U$11") (pin "PD1") (pinfunction "PD1_PD1") (pintype "bidirectional"))
    )
    (net (code "82") (name "Net-(U$10-PadI3)") (class "Default")
      (node (ref "U$10") (pin "I3") (pinfunction "I3_I3") (pintype "bidirectional"))
      (node (ref "U$11") (pin "PD2") (pinfunction "PD2_PD2") (pintype "bidirectional"))
    )
    (net (code "83") (name "Net-(U$10-PadI4)") (class "Default")
      (node (ref "U$10") (pin "I4") (pinfunction "I4_I4") (pintype "bidirectional"))
      (node (ref "U$11") (pin "PD3") (pinfunction "PD3_PD3") (pintype "bidirectional"))
    )
    (net (code "84") (name "Net-(U$10-PadI5)") (class "Default")
      (node (ref "U$10") (pin "I5") (pinfunction "I5_I5") (pintype "bidirectional"))
      (node (ref "U$11") (pin "PD4") (pinfunction "PD4_PD4") (pintype "bidirectional"))
    )
    (net (code "85") (name "Net-(U$10-PadI6)") (class "Default")
      (node (ref "U$10") (pin "I6") (pinfunction "I6_I6") (pintype "bidirectional"))
      (node (ref "U$11") (pin "PD5") (pinfunction "PD5_PD5") (pintype "bidirectional"))
    )
    (net (code "86") (name "Net-(U$10-PadI7)") (class "Default")
      (node (ref "U$10") (pin "I7") (pinfunction "I7_I7") (pintype "bidirectional"))
      (node (ref "U$11") (pin "PD6") (pinfunction "PD6_PD6") (pintype "bidirectional"))
    )
    (net (code "87") (name "Net-(U$10-PadI8)") (class "Default")
      (node (ref "U$10") (pin "I8") (pinfunction "I8_I8") (pintype "bidirectional"))
      (node (ref "U$11") (pin "PD7") (pinfunction "PD7_PD7") (pintype "bidirectional"))
    )
    (net (code "88") (name "Net-(U$10-PadO1)") (class "Default")
      (node (ref "U$10") (pin "O1") (pinfunction "O1_O1") (pintype "bidirectional"))
      (node (ref "U$8") (pin "COL0") (pinfunction "COL0_COL0") (pintype "bidirectional"))
    )
    (net (code "89") (name "Net-(U$10-PadO2)") (class "Default")
      (node (ref "U$10") (pin "O2") (pinfunction "O2_O2") (pintype "bidirectional"))
      (node (ref "U$8") (pin "COL1") (pinfunction "COL1_COL1") (pintype "bidirectional"))
    )
    (net (code "90") (name "Net-(U$10-PadO3)") (class "Default")
      (node (ref "U$10") (pin "O3") (pinfunction "O3_O3") (pintype "bidirectional"))
      (node (ref "U$8") (pin "COL2") (pinfunction "COL2_COL2") (pintype "bidirectional"))
    )
    (net (code "91") (name "Net-(U$10-PadO4)") (class "Default")
      (node (ref "U$10") (pin "O4") (pinfunction "O4_O4") (pintype "bidirectional"))
      (node (ref "U$8") (pin "COL3") (pinfunction "COL3_COL3") (pintype "bidirectional"))
    )
    (net (code "92") (name "Net-(U$10-PadO5)") (class "Default")
      (node (ref "U$10") (pin "O5") (pinfunction "O5_O5") (pintype "bidirectional"))
      (node (ref "U$8") (pin "COL4") (pinfunction "COL4_COL4") (pintype "bidirectional"))
    )
    (net (code "93") (name "Net-(U$10-PadO6)") (class "Default")
      (node (ref "U$10") (pin "O6") (pinfunction "O6_O6") (pintype "bidirectional"))
      (node (ref "U$8") (pin "COL5") (pinfunction "COL5_COL5") (pintype "bidirectional"))
    )
    (net (code "94") (name "Net-(U$10-PadO7)") (class "Default")
      (node (ref "U$10") (pin "O7") (pinfunction "O7_O7") (pintype "bidirectional"))
      (node (ref "U$8") (pin "COL6") (pinfunction "COL6_COL6") (pintype "bidirectional"))
    )
    (net (code "95") (name "Net-(U$10-PadO8)") (class "Default")
      (node (ref "U$10") (pin "O8") (pinfunction "O8_O8") (pintype "bidirectional"))
      (node (ref "U$8") (pin "COL7") (pinfunction "COL7_COL7") (pintype "bidirectional"))
    )
    (net (code "96") (name "Net-(U$11-PadPA1)") (class "Default")
      (node (ref "U$11") (pin "PA1") (pinfunction "PA1_PA1") (pintype "bidirectional"))
      (node (ref "U$12") (pin "R7") (pinfunction "R7_R7") (pintype "bidirectional"))
    )
    (net (code "97") (name "Net-(U$11-PadPC0)") (class "Default")
      (node (ref "U$11") (pin "PC0") (pinfunction "PC0_PC0") (pintype "bidirectional"))
      (node (ref "U$12") (pin "R6") (pinfunction "R6_R6") (pintype "bidirectional"))
    )
    (net (code "98") (name "Net-(U$11-PadPC1)") (class "Default")
      (node (ref "U$11") (pin "PC1") (pinfunction "PC1_PC1") (pintype "bidirectional"))
      (node (ref "U$12") (pin "R5") (pinfunction "R5_R5") (pintype "bidirectional"))
    )
    (net (code "99") (name "Net-(U$11-PadPC2)") (class "Default")
      (node (ref "U$11") (pin "PC2") (pinfunction "PC2_PC2") (pintype "bidirectional"))
      (node (ref "U$12") (pin "R4") (pinfunction "R4_R4") (pintype "bidirectional"))
    )
    (net (code "100") (name "Net-(U$11-PadPC3)") (class "Default")
      (node (ref "U$11") (pin "PC3") (pinfunction "PC3_PC3") (pintype "bidirectional"))
      (node (ref "U$12") (pin "R3") (pinfunction "R3_R3") (pintype "bidirectional"))
    )
    (net (code "101") (name "Net-(U$11-PadPC4)") (class "Default")
      (node (ref "U$11") (pin "PC4") (pinfunction "PC4_PC4") (pintype "bidirectional"))
      (node (ref "U$12") (pin "R2") (pinfunction "R2_R2") (pintype "bidirectional"))
    )
    (net (code "102") (name "Net-(U$11-PadPC5)") (class "Default")
      (node (ref "U$11") (pin "PC5") (pinfunction "PC5_PC5") (pintype "bidirectional"))
      (node (ref "U$12") (pin "R1") (pinfunction "R1_R1") (pintype "bidirectional"))
    )
    (net (code "103") (name "Net-(U$11-PadPC7)") (class "Default")
      (node (ref "U$11") (pin "PC7") (pinfunction "PC7_PC7") (pintype "bidirectional"))
      (node (ref "U$12") (pin "R8") (pinfunction "R8_R8") (pintype "bidirectional"))
    )
    (net (code "104") (name "Net-(U$12-Pad1R)") (class "Default")
      (node (ref "U$12") (pin "1R") (pinfunction "1R_1R") (pintype "bidirectional"))
      (node (ref "U$8") (pin "ROW7") (pinfunction "ROW7_ROW7") (pintype "bidirectional"))
    )
    (net (code "105") (name "Net-(U$12-Pad2R)") (class "Default")
      (node (ref "U$12") (pin "2R") (pinfunction "2R_2R") (pintype "bidirectional"))
      (node (ref "U$8") (pin "ROW6") (pinfunction "ROW6_ROW6") (pintype "bidirectional"))
    )
    (net (code "106") (name "Net-(U$12-Pad3R)") (class "Default")
      (node (ref "U$12") (pin "3R") (pinfunction "3R_3R") (pintype "bidirectional"))
      (node (ref "U$8") (pin "ROW5") (pinfunction "ROW5_ROW5") (pintype "bidirectional"))
    )
    (net (code "107") (name "Net-(U$12-Pad4R)") (class "Default")
      (node (ref "U$12") (pin "4R") (pinfunction "4R_4R") (pintype "bidirectional"))
      (node (ref "U$8") (pin "ROW4") (pinfunction "ROW4_ROW4") (pintype "bidirectional"))
    )
    (net (code "108") (name "Net-(U$12-Pad5R)") (class "Default")
      (node (ref "U$12") (pin "5R") (pinfunction "5R_5R") (pintype "bidirectional"))
      (node (ref "U$8") (pin "ROW3") (pinfunction "ROW3_ROW3") (pintype "bidirectional"))
    )
    (net (code "109") (name "Net-(U$12-Pad6R)") (class "Default")
      (node (ref "U$12") (pin "6R") (pinfunction "6R_6R") (pintype "bidirectional"))
      (node (ref "U$8") (pin "ROW2") (pinfunction "ROW2_ROW2") (pintype "bidirectional"))
    )
    (net (code "110") (name "Net-(U$12-Pad7R)") (class "Default")
      (node (ref "U$12") (pin "7R") (pinfunction "7R_7R") (pintype "bidirectional"))
      (node (ref "U$8") (pin "ROW1") (pinfunction "ROW1_ROW1") (pintype "bidirectional"))
    )
    (net (code "111") (name "Net-(U$12-Pad8R)") (class "Default")
      (node (ref "U$12") (pin "8R") (pinfunction "8R_8R") (pintype "bidirectional"))
      (node (ref "U$8") (pin "ROW0") (pinfunction "ROW0_ROW0") (pintype "bidirectional"))
    )
    (net (code "112") (name "Net-(U$13-PadCOL0)") (class "Default")
      (node (ref "U$13") (pin "COL0") (pinfunction "COL0_COL0") (pintype "bidirectional"))
      (node (ref "U$14") (pin "O1") (pinfunction "O1_O1") (pintype "bidirectional"))
    )
    (net (code "113") (name "Net-(U$13-PadCOL1)") (class "Default")
      (node (ref "U$13") (pin "COL1") (pinfunction "COL1_COL1") (pintype "bidirectional"))
      (node (ref "U$14") (pin "O2") (pinfunction "O2_O2") (pintype "bidirectional"))
    )
    (net (code "114") (name "Net-(U$13-PadCOL2)") (class "Default")
      (node (ref "U$13") (pin "COL2") (pinfunction "COL2_COL2") (pintype "bidirectional"))
      (node (ref "U$14") (pin "O3") (pinfunction "O3_O3") (pintype "bidirectional"))
    )
    (net (code "115") (name "Net-(U$13-PadCOL3)") (class "Default")
      (node (ref "U$13") (pin "COL3") (pinfunction "COL3_COL3") (pintype "bidirectional"))
      (node (ref "U$14") (pin "O4") (pinfunction "O4_O4") (pintype "bidirectional"))
    )
    (net (code "116") (name "Net-(U$13-PadCOL4)") (class "Default")
      (node (ref "U$13") (pin "COL4") (pinfunction "COL4_COL4") (pintype "bidirectional"))
      (node (ref "U$14") (pin "O5") (pinfunction "O5_O5") (pintype "bidirectional"))
    )
    (net (code "117") (name "Net-(U$13-PadCOL5)") (class "Default")
      (node (ref "U$13") (pin "COL5") (pinfunction "COL5_COL5") (pintype "bidirectional"))
      (node (ref "U$14") (pin "O6") (pinfunction "O6_O6") (pintype "bidirectional"))
    )
    (net (code "118") (name "Net-(U$13-PadCOL6)") (class "Default")
      (node (ref "U$13") (pin "COL6") (pinfunction "COL6_COL6") (pintype "bidirectional"))
      (node (ref "U$14") (pin "O7") (pinfunction "O7_O7") (pintype "bidirectional"))
    )
    (net (code "119") (name "Net-(U$13-PadCOL7)") (class "Default")
      (node (ref "U$13") (pin "COL7") (pinfunction "COL7_COL7") (pintype "bidirectional"))
      (node (ref "U$14") (pin "O8") (pinfunction "O8_O8") (pintype "bidirectional"))
    )
    (net (code "120") (name "Net-(U$13-PadROW0)") (class "Default")
      (node (ref "U$13") (pin "ROW0") (pinfunction "ROW0_ROW0") (pintype "bidirectional"))
      (node (ref "U$16") (pin "8R") (pinfunction "8R_8R") (pintype "bidirectional"))
    )
    (net (code "121") (name "Net-(U$13-PadROW1)") (class "Default")
      (node (ref "U$13") (pin "ROW1") (pinfunction "ROW1_ROW1") (pintype "bidirectional"))
      (node (ref "U$16") (pin "7R") (pinfunction "7R_7R") (pintype "bidirectional"))
    )
    (net (code "122") (name "Net-(U$13-PadROW2)") (class "Default")
      (node (ref "U$13") (pin "ROW2") (pinfunction "ROW2_ROW2") (pintype "bidirectional"))
      (node (ref "U$16") (pin "6R") (pinfunction "6R_6R") (pintype "bidirectional"))
    )
    (net (code "123") (name "Net-(U$13-PadROW3)") (class "Default")
      (node (ref "U$13") (pin "ROW3") (pinfunction "ROW3_ROW3") (pintype "bidirectional"))
      (node (ref "U$16") (pin "5R") (pinfunction "5R_5R") (pintype "bidirectional"))
    )
    (net (code "124") (name "Net-(U$13-PadROW4)") (class "Default")
      (node (ref "U$13") (pin "ROW4") (pinfunction "ROW4_ROW4") (pintype "bidirectional"))
      (node (ref "U$16") (pin "4R") (pinfunction "4R_4R") (pintype "bidirectional"))
    )
    (net (code "125") (name "Net-(U$13-PadROW5)") (class "Default")
      (node (ref "U$13") (pin "ROW5") (pinfunction "ROW5_ROW5") (pintype "bidirectional"))
      (node (ref "U$16") (pin "3R") (pinfunction "3R_3R") (pintype "bidirectional"))
    )
    (net (code "126") (name "Net-(U$13-PadROW6)") (class "Default")
      (node (ref "U$13") (pin "ROW6") (pinfunction "ROW6_ROW6") (pintype "bidirectional"))
      (node (ref "U$16") (pin "2R") (pinfunction "2R_2R") (pintype "bidirectional"))
    )
    (net (code "127") (name "Net-(U$13-PadROW7)") (class "Default")
      (node (ref "U$13") (pin "ROW7") (pinfunction "ROW7_ROW7") (pintype "bidirectional"))
      (node (ref "U$16") (pin "1R") (pinfunction "1R_1R") (pintype "bidirectional"))
    )
    (net (code "128") (name "Net-(U$14-PadI1)") (class "Default")
      (node (ref "U$14") (pin "I1") (pinfunction "I1_I1") (pintype "bidirectional"))
      (node (ref "U$15") (pin "PD0") (pinfunction "PD0_PD0") (pintype "bidirectional"))
    )
    (net (code "129") (name "Net-(U$14-PadI2)") (class "Default")
      (node (ref "U$14") (pin "I2") (pinfunction "I2_I2") (pintype "bidirectional"))
      (node (ref "U$15") (pin "PD1") (pinfunction "PD1_PD1") (pintype "bidirectional"))
    )
    (net (code "130") (name "Net-(U$14-PadI3)") (class "Default")
      (node (ref "U$14") (pin "I3") (pinfunction "I3_I3") (pintype "bidirectional"))
      (node (ref "U$15") (pin "PD2") (pinfunction "PD2_PD2") (pintype "bidirectional"))
    )
    (net (code "131") (name "Net-(U$14-PadI4)") (class "Default")
      (node (ref "U$14") (pin "I4") (pinfunction "I4_I4") (pintype "bidirectional"))
      (node (ref "U$15") (pin "PD3") (pinfunction "PD3_PD3") (pintype "bidirectional"))
    )
    (net (code "132") (name "Net-(U$14-PadI5)") (class "Default")
      (node (ref "U$14") (pin "I5") (pinfunction "I5_I5") (pintype "bidirectional"))
      (node (ref "U$15") (pin "PD4") (pinfunction "PD4_PD4") (pintype "bidirectional"))
    )
    (net (code "133") (name "Net-(U$14-PadI6)") (class "Default")
      (node (ref "U$14") (pin "I6") (pinfunction "I6_I6") (pintype "bidirectional"))
      (node (ref "U$15") (pin "PD5") (pinfunction "PD5_PD5") (pintype "bidirectional"))
    )
    (net (code "134") (name "Net-(U$14-PadI7)") (class "Default")
      (node (ref "U$14") (pin "I7") (pinfunction "I7_I7") (pintype "bidirectional"))
      (node (ref "U$15") (pin "PD6") (pinfunction "PD6_PD6") (pintype "bidirectional"))
    )
    (net (code "135") (name "Net-(U$14-PadI8)") (class "Default")
      (node (ref "U$14") (pin "I8") (pinfunction "I8_I8") (pintype "bidirectional"))
      (node (ref "U$15") (pin "PD7") (pinfunction "PD7_PD7") (pintype "bidirectional"))
    )
    (net (code "136") (name "Net-(U$15-PadPA1)") (class "Default")
      (node (ref "U$15") (pin "PA1") (pinfunction "PA1_PA1") (pintype "bidirectional"))
      (node (ref "U$16") (pin "R7") (pinfunction "R7_R7") (pintype "bidirectional"))
    )
    (net (code "137") (name "Net-(U$15-PadPC0)") (class "Default")
      (node (ref "U$15") (pin "PC0") (pinfunction "PC0_PC0") (pintype "bidirectional"))
      (node (ref "U$16") (pin "R6") (pinfunction "R6_R6") (pintype "bidirectional"))
    )
    (net (code "138") (name "Net-(U$15-PadPC1)") (class "Default")
      (node (ref "U$15") (pin "PC1") (pinfunction "PC1_PC1") (pintype "bidirectional"))
      (node (ref "U$16") (pin "R5") (pinfunction "R5_R5") (pintype "bidirectional"))
    )
    (net (code "139") (name "Net-(U$15-PadPC2)") (class "Default")
      (node (ref "U$15") (pin "PC2") (pinfunction "PC2_PC2") (pintype "bidirectional"))
      (node (ref "U$16") (pin "R4") (pinfunction "R4_R4") (pintype "bidirectional"))
    )
    (net (code "140") (name "Net-(U$15-PadPC3)") (class "Default")
      (node (ref "U$15") (pin "PC3") (pinfunction "PC3_PC3") (pintype "bidirectional"))
      (node (ref "U$16") (pin "R3") (pinfunction "R3_R3") (pintype "bidirectional"))
    )
    (net (code "141") (name "Net-(U$15-PadPC4)") (class "Default")
      (node (ref "U$15") (pin "PC4") (pinfunction "PC4_PC4") (pintype "bidirectional"))
      (node (ref "U$16") (pin "R2") (pinfunction "R2_R2") (pintype "bidirectional"))
    )
    (net (code "142") (name "Net-(U$15-PadPC5)") (class "Default")
      (node (ref "U$15") (pin "PC5") (pinfunction "PC5_PC5") (pintype "bidirectional"))
      (node (ref "U$16") (pin "R1") (pinfunction "R1_R1") (pintype "bidirectional"))
    )
    (net (code "143") (name "Net-(U$15-PadPC7)") (class "Default")
      (node (ref "U$15") (pin "PC7") (pinfunction "PC7_PC7") (pintype "bidirectional"))
      (node (ref "U$16") (pin "R8") (pinfunction "R8_R8") (pintype "bidirectional"))
    )
    (net (code "144") (name "Net-(U$23-BYP)") (class "Default")
      (node (ref "C3") (pin "1") (pinfunction "1_1") (pintype "passive"))
      (node (ref "U$23") (pin "4") (pinfunction "BYP_4") (pintype "bidirectional"))
    )
    (net (code "145") (name "Net-(U$25-BYPASS)") (class "Default")
      (node (ref "C7") (pin "1") (pinfunction "1_1") (pintype "passive"))
      (node (ref "U$25") (pin "7") (pinfunction "BYPASS_7") (pintype "bidirectional"))
    )
    (net (code "146") (name "Net-(U$25-VOUT)") (class "Default")
      (node (ref "C5") (pin "+") (pinfunction "+_+") (pintype "passive"))
      (node (ref "C6") (pin "1") (pinfunction "1_1") (pintype "passive"))
      (node (ref "U$25") (pin "5") (pinfunction "VOUT_5") (pintype "bidirectional"))
    )
    (net (code "147") (name "RESET") (class "Default")
      (node (ref "J1") (pin "5") (pinfunction "5_5") (pintype "passive"))
      (node (ref "J2") (pin "5") (pinfunction "5_5") (pintype "passive"))
      (node (ref "J3") (pin "5") (pinfunction "5_5") (pintype "passive"))
      (node (ref "J4") (pin "5") (pinfunction "5_5") (pintype "passive"))
      (node (ref "PI-HEADER") (pin "22") (pinfunction "22_22") (pintype "passive"))
      (node (ref "R10") (pin "1") (pinfunction "1_1") (pintype "passive"))
      (node (ref "R5") (pin "1") (pinfunction "1_1") (pintype "passive"))
      (node (ref "R6") (pin "1") (pinfunction "1_1") (pintype "passive"))
      (node (ref "R8") (pin "1") (pinfunction "1_1") (pintype "passive"))
      (node (ref "U$11") (pin "PC6") (pinfunction "PC6_PC6") (pintype "bidirectional"))
      (node (ref "U$15") (pin "PC6") (pinfunction "PC6_PC6") (pintype "bidirectional"))
      (node (ref "U$6") (pin "PC6") (pinfunction "PC6_PC6") (pintype "bidirectional"))
      (node (ref "U$9") (pin "PC6") (pinfunction "PC6_PC6") (pintype "bidirectional"))
    )
    (net (code "148") (name "RIGHT") (class "Default")
      (node (ref "PI-HEADER") (pin "18") (pinfunction "18_18") (pintype "passive"))
      (node (ref "U$19") (pin "2") (pinfunction "2_2") (pintype "bidirectional"))
    )
    (net (code "149") (name "SCK") (class "Default")
      (node (ref "J1") (pin "3") (pinfunction "3_3") (pintype "passive"))
      (node (ref "J2") (pin "3") (pinfunction "3_3") (pintype "passive"))
      (node (ref "J3") (pin "3") (pinfunction "3_3") (pintype "passive"))
      (node (ref "J4") (pin "3") (pinfunction "3_3") (pintype "passive"))
      (node (ref "PI-HEADER") (pin "23") (pinfunction "23_23") (pintype "passive"))
      (node (ref "U$11") (pin "PB5") (pinfunction "PB5_PB5") (pintype "bidirectional"))
      (node (ref "U$15") (pin "PB5") (pinfunction "PB5_PB5") (pintype "bidirectional"))
      (node (ref "U$6") (pin "PB5") (pinfunction "PB5_PB5") (pintype "bidirectional"))
      (node (ref "U$9") (pin "PB5") (pinfunction "PB5_PB5") (pintype "bidirectional"))
    )
    (net (code "150") (name "SCL") (class "Default")
      (node (ref "PI-HEADER") (pin "5") (pinfunction "5_5") (pintype "passive"))
      (node (ref "R2") (pin "2") (pinfunction "2_2") (pintype "passive"))
      (node (ref "U$23") (pin "2") (pinfunction "SCL_2") (pintype "bidirectional"))
    )
    (net (code "151") (name "SDA") (class "Default")
      (node (ref "PI-HEADER") (pin "3") (pinfunction "3_3") (pintype "passive"))
      (node (ref "R1") (pin "1") (pinfunction "1_1") (pintype "passive"))
      (node (ref "U$23") (pin "10") (pinfunction "SDA_10") (pintype "bidirectional"))
    )
    (net (code "152") (name "SPK") (class "Default")
      (node (ref "C5") (pin "-") (pinfunction "-_-") (pintype "passive"))
      (node (ref "U$29") (pin "1") (pinfunction "1_1") (pintype "bidirectional"))
    )
    (net (code "153") (name "SS") (class "Default")
      (node (ref "U$11") (pin "PB2") (pinfunction "PB2_PB2") (pintype "bidirectional"))
      (node (ref "U$15") (pin "PB2") (pinfunction "PB2_PB2") (pintype "bidirectional"))
      (node (ref "U$6") (pin "PB2") (pinfunction "PB2_PB2") (pintype "bidirectional"))
      (node (ref "U$9") (pin "PB2") (pinfunction "PB2_PB2") (pintype "bidirectional"))
    )
    (net (code "154") (name "UP") (class "Default")
      (node (ref "PI-HEADER") (pin "7") (pinfunction "7_7") (pintype "passive"))
      (node (ref "U$17") (pin "2") (pinfunction "2_2") (pintype "bidirectional"))
    )
    (net (code "155") (name "VCC") (class "Default")
      (node (ref "C1") (pin "1") (pinfunction "1_1") (pintype "passive"))
      (node (ref "C2") (pin "1") (pinfunction "1_1") (pintype "passive"))
      (node (ref "C4") (pin "1") (pinfunction "1_1") (pintype "passive"))
      (node (ref "J1") (pin "2") (pinfunction "2_2") (pintype "passive"))
      (node (ref "J2") (pin "2") (pinfunction "2_2") (pintype "passive"))
      (node (ref "J3") (pin "2") (pinfunction "2_2") (pintype "passive"))
      (node (ref "J4") (pin "2") (pinfunction "2_2") (pintype "passive"))
      (node (ref "R1") (pin "2") (pinfunction "2_2") (pintype "passive"))
      (node (ref "R10") (pin "2") (pinfunction "2_2") (pintype "passive"))
      (node (ref "R2") (pin "1") (pinfunction "1_1") (pintype "passive"))
      (node (ref "R5") (pin "2") (pinfunction "2_2") (pintype "passive"))
      (node (ref "R6") (pin "2") (pinfunction "2_2") (pintype "passive"))
      (node (ref "R8") (pin "2") (pinfunction "2_2") (pintype "passive"))
      (node (ref "U$10") (pin "COMMON") (pinfunction "COMMON_COMMON") (pintype "bidirectional"))
      (node (ref "U$11") (pin "AVCC") (pinfunction "AVCC_AVCC") (pintype "bidirectional"))
      (node (ref "U$11") (pin "VCC") (pinfunction "VCC_VCC") (pintype "bidirectional"))
      (node (ref "U$14") (pin "COMMON") (pinfunction "COMMON_COMMON") (pintype "bidirectional"))
      (node (ref "U$15") (pin "AVCC") (pinfunction "AVCC_AVCC") (pintype "bidirectional"))
      (node (ref "U$15") (pin "VCC") (pinfunction "VCC_VCC") (pintype "bidirectional"))
      (node (ref "U$23") (pin "1") (pinfunction "VDD_1") (pintype "bidirectional"))
      (node (ref "U$23") (pin "8") (pinfunction "VDDIO_8") (pintype "bidirectional"))
      (node (ref "U$25") (pin "6") (pinfunction "VS_6") (pintype "bidirectional"))
      (node (ref "U$30") (pin "4") (pinfunction "4_4") (pintype "bidirectional"))
      (node (ref "U$4") (pin "COMMON") (pinfunction "COMMON_COMMON") (pintype "bidirectional"))
      (node (ref "U$5") (pin "COMMON") (pinfunction "COMMON_COMMON") (pintype "bidirectional"))
      (node (ref "U$6") (pin "AVCC") (pinfunction "AVCC_AVCC") (pintype "bidirectional"))
      (node (ref "U$6") (pin "VCC") (pinfunction "VCC_VCC") (pintype "bidirectional"))
      (node (ref "U$9") (pin "AVCC") (pinfunction "AVCC_AVCC") (pintype "bidirectional"))
      (node (ref "U$9") (pin "VCC") (pinfunction "VCC_VCC") (pintype "bidirectional"))
    )
    (net (code "156") (name "unconnected-(PI-HEADER-Pad1)") (class "Default")
      (node (ref "PI-HEADER") (pin "1") (pinfunction "1_1") (pintype "passive"))
    )
    (net (code "157") (name "unconnected-(PI-HEADER-Pad2)") (class "Default")
      (node (ref "PI-HEADER") (pin "2") (pinfunction "2_2") (pintype "passive"))
    )
    (net (code "158") (name "unconnected-(PI-HEADER-Pad4)") (class "Default")
      (node (ref "PI-HEADER") (pin "4") (pinfunction "4_4") (pintype "passive"))
    )
    (net (code "159") (name "unconnected-(PI-HEADER-Pad9)") (class "Default")
      (node (ref "PI-HEADER") (pin "9") (pinfunction "9_9") (pintype "passive"))
    )
    (net (code "160") (name "unconnected-(PI-HEADER-Pad11)") (class "Default")
      (node (ref "PI-HEADER") (pin "11") (pinfunction "11_11") (pintype "passive"))
    )
    (net (code "161") (name "unconnected-(PI-HEADER-Pad14)") (class "Default")
      (node (ref "PI-HEADER") (pin "14") (pinfunction "14_14") (pintype "passive"))
    )
    (net (code "162") (name "unconnected-(PI-HEADER-Pad17)") (class "Default")
      (node (ref "PI-HEADER") (pin "17") (pinfunction "17_17") (pintype "passive"))
    )
    (net (code "163") (name "unconnected-(PI-HEADER-Pad20)") (class "Default")
      (node (ref "PI-HEADER") (pin "20") (pinfunction "20_20") (pintype "passive"))
    )
    (net (code "164") (name "unconnected-(PI-HEADER-Pad24)") (class "Default")
      (node (ref "PI-HEADER") (pin "24") (pinfunction "24_24") (pintype "passive"))
    )
    (net (code "165") (name "unconnected-(PI-HEADER-Pad25)") (class "Default")
      (node (ref "PI-HEADER") (pin "25") (pinfunction "25_25") (pintype "passive"))
    )
    (net (code "166") (name "unconnected-(PI-HEADER-Pad26)") (class "Default")
      (node (ref "PI-HEADER") (pin "26") (pinfunction "26_26") (pintype "passive"))
    )
    (net (code "167") (name "unconnected-(U$6-PadPA0)") (class "Default")
      (node (ref "U$6") (pin "PA0") (pinfunction "PA0_PA0") (pintype "bidirectional"))
    )
    (net (code "168") (name "unconnected-(U$6-PadPA2)") (class "Default")
      (node (ref "U$6") (pin "PA2") (pinfunction "PA2_PA2") (pintype "bidirectional"))
    )
    (net (code "169") (name "unconnected-(U$6-PadPA3)") (class "Default")
      (node (ref "U$6") (pin "PA3") (pinfunction "PA3_PA3") (pintype "bidirectional"))
    )
    (net (code "170") (name "unconnected-(U$6-PadPB0)") (class "Default")
      (node (ref "U$6") (pin "PB0") (pinfunction "PB0_PB0") (pintype "bidirectional"))
    )
    (net (code "171") (name "unconnected-(U$6-PadPB1)") (class "Default")
      (node (ref "U$6") (pin "PB1") (pinfunction "PB1_PB1") (pintype "bidirectional"))
    )
    (net (code "172") (name "unconnected-(U$6-PadPB6)") (class "Default")
      (node (ref "U$6") (pin "PB6") (pinfunction "PB6_PB6") (pintype "bidirectional"))
    )
    (net (code "173") (name "unconnected-(U$6-PadPB7)") (class "Default")
      (node (ref "U$6") (pin "PB7") (pinfunction "PB7_PB7") (pintype "bidirectional"))
    )
    (net (code "174") (name "unconnected-(U$9-PadPA0)") (class "Default")
      (node (ref "U$9") (pin "PA0") (pinfunction "PA0_PA0") (pintype "bidirectional"))
    )
    (net (code "175") (name "unconnected-(U$9-PadPA2)") (class "Default")
      (node (ref "U$9") (pin "PA2") (pinfunction "PA2_PA2") (pintype "bidirectional"))
    )
    (net (code "176") (name "unconnected-(U$9-PadPA3)") (class "Default")
      (node (ref "U$9") (pin "PA3") (pinfunction "PA3_PA3") (pintype "bidirectional"))
    )
    (net (code "177") (name "unconnected-(U$9-PadPB0)") (class "Default")
      (node (ref "U$9") (pin "PB0") (pinfunction "PB0_PB0") (pintype "bidirectional"))
    )
    (net (code "178") (name "unconnected-(U$9-PadPB1)") (class "Default")
      (node (ref "U$9") (pin "PB1") (pinfunction "PB1_PB1") (pintype "bidirectional"))
    )
    (net (code "179") (name "unconnected-(U$9-PadPB6)") (class "Default")
      (node (ref "U$9") (pin "PB6") (pinfunction "PB6_PB6") (pintype "bidirectional"))
    )
    (net (code "180") (name "unconnected-(U$9-PadPB7)") (class "Default")
      (node (ref "U$9") (pin "PB7") (pinfunction "PB7_PB7") (pintype "bidirectional"))
    )
    (net (code "181") (name "unconnected-(U$11-PadPA0)") (class "Default")
      (node (ref "U$11") (pin "PA0") (pinfunction "PA0_PA0") (pintype "bidirectional"))
    )
    (net (code "182") (name "unconnected-(U$11-PadPA2)") (class "Default")
      (node (ref "U$11") (pin "PA2") (pinfunction "PA2_PA2") (pintype "bidirectional"))
    )
    (net (code "183") (name "unconnected-(U$11-PadPA3)") (class "Default")
      (node (ref "U$11") (pin "PA3") (pinfunction "PA3_PA3") (pintype "bidirectional"))
    )
    (net (code "184") (name "unconnected-(U$11-PadPB0)") (class "Default")
      (node (ref "U$11") (pin "PB0") (pinfunction "PB0_PB0") (pintype "bidirectional"))
    )
    (net (code "185") (name "unconnected-(U$11-PadPB1)") (class "Default")
      (node (ref "U$11") (pin "PB1") (pinfunction "PB1_PB1") (pintype "bidirectional"))
    )
    (net (code "186") (name "unconnected-(U$11-PadPB6)") (class "Default")
      (node (ref "U$11") (pin "PB6") (pinfunction "PB6_PB6") (pintype "bidirectional"))
    )
    (net (code "187") (name "unconnected-(U$11-PadPB7)") (class "Default")
      (node (ref "U$11") (pin "PB7") (pinfunction "PB7_PB7") (pintype "bidirectional"))
    )
    (net (code "188") (name "unconnected-(U$15-PadPA0)") (class "Default")
      (node (ref "U$15") (pin "PA0") (pinfunction "PA0_PA0") (pintype "bidirectional"))
    )
    (net (code "189") (name "unconnected-(U$15-PadPA2)") (class "Default")
      (node (ref "U$15") (pin "PA2") (pinfunction "PA2_PA2") (pintype "bidirectional"))
    )
    (net (code "190") (name "unconnected-(U$15-PadPA3)") (class "Default")
      (node (ref "U$15") (pin "PA3") (pinfunction "PA3_PA3") (pintype "bidirectional"))
    )
    (net (code "191") (name "unconnected-(U$15-PadPB0)") (class "Default")
      (node (ref "U$15") (pin "PB0") (pinfunction "PB0_PB0") (pintype "bidirectional"))
    )
    (net (code "192") (name "unconnected-(U$15-PadPB1)") (class "Default")
      (node (ref "U$15") (pin "PB1") (pinfunction "PB1_PB1") (pintype "bidirectional"))
    )
    (net (code "193") (name "unconnected-(U$15-PadPB6)") (class "Default")
      (node (ref "U$15") (pin "PB6") (pinfunction "PB6_PB6") (pintype "bidirectional"))
    )
    (net (code "194") (name "unconnected-(U$15-PadPB7)") (class "Default")
      (node (ref "U$15") (pin "PB7") (pinfunction "PB7_PB7") (pintype "bidirectional"))
    )
    (net (code "195") (name "unconnected-(U$17-Pad1)") (class "Default")
      (node (ref "U$17") (pin "1") (pinfunction "1_1") (pintype "bidirectional"))
    )
    (net (code "196") (name "unconnected-(U$17-Pad3)") (class "Default")
      (node (ref "U$17") (pin "3") (pinfunction "3_3") (pintype "bidirectional"))
    )
    (net (code "197") (name "unconnected-(U$18-Pad1)") (class "Default")
      (node (ref "U$18") (pin "1") (pinfunction "1_1") (pintype "bidirectional"))
    )
    (net (code "198") (name "unconnected-(U$18-Pad3)") (class "Default")
      (node (ref "U$18") (pin "3") (pinfunction "3_3") (pintype "bidirectional"))
    )
    (net (code "199") (name "unconnected-(U$19-Pad1)") (class "Default")
      (node (ref "U$19") (pin "1") (pinfunction "1_1") (pintype "bidirectional"))
    )
    (net (code "200") (name "unconnected-(U$19-Pad3)") (class "Default")
      (node (ref "U$19") (pin "3") (pinfunction "3_3") (pintype "bidirectional"))
    )
    (net (code "201") (name "unconnected-(U$20-Pad1)") (class "Default")
      (node (ref "U$20") (pin "1") (pinfunction "1_1") (pintype "bidirectional"))
    )
    (net (code "202") (name "unconnected-(U$20-Pad3)") (class "Default")
      (node (ref "U$20") (pin "3") (pinfunction "3_3") (pintype "bidirectional"))
    )
    (net (code "203") (name "unconnected-(U$21-Pad2)") (class "Default")
      (node (ref "U$21") (pin "2") (pinfunction "2_2") (pintype "bidirectional"))
    )
    (net (code "204") (name "unconnected-(U$21-Pad4)") (class "Default")
      (node (ref "U$21") (pin "4") (pinfunction "4_4") (pintype "bidirectional"))
    )
    (net (code "205") (name "unconnected-(U$22-Pad2)") (class "Default")
      (node (ref "U$22") (pin "2") (pinfunction "2_2") (pintype "bidirectional"))
    )
    (net (code "206") (name "unconnected-(U$22-Pad4)") (class "Default")
      (node (ref "U$22") (pin "4") (pinfunction "4_4") (pintype "bidirectional"))
    )
    (net (code "207") (name "unconnected-(U$25-GAIN1-Pad1)") (class "Default")
      (node (ref "U$25") (pin "1") (pinfunction "GAIN1_1") (pintype "bidirectional"))
    )
    (net (code "208") (name "unconnected-(U$25-GAIN2-Pad8)") (class "Default")
      (node (ref "U$25") (pin "8") (pinfunction "GAIN2_8") (pintype "bidirectional"))
    )
    (net (code "209") (name "unconnected-(U$30-Pad3)") (class "Default")
      (node (ref "U$30") (pin "3") (pinfunction "3_3") (pintype "bidirectional"))
    )
  )
)
